# trailmon.net
KiCad netlist of a schematic drawn in EAGLE
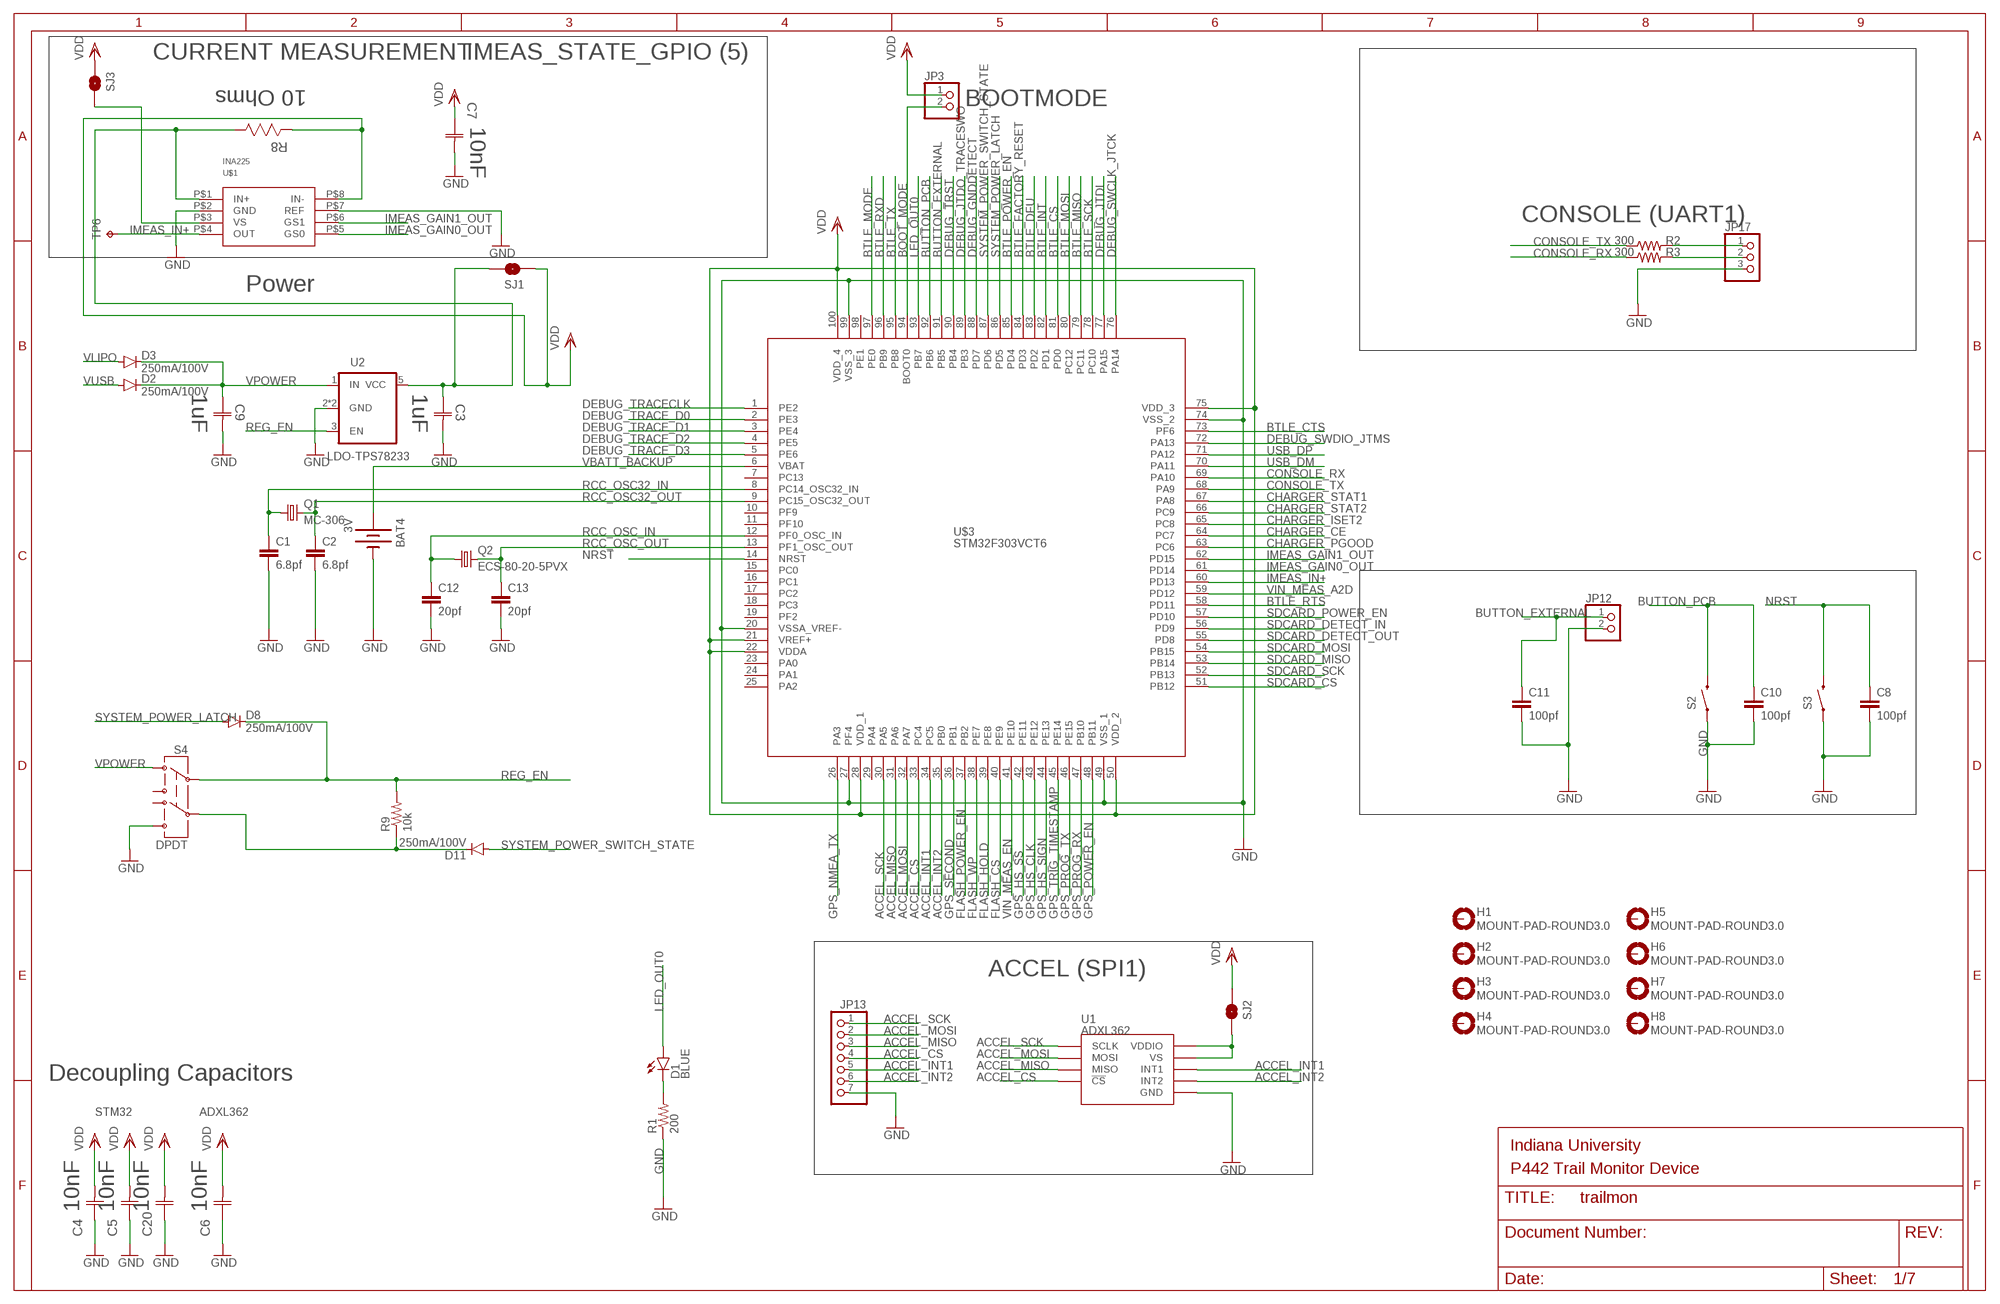
[diagram p0: schematic, sheet 1]
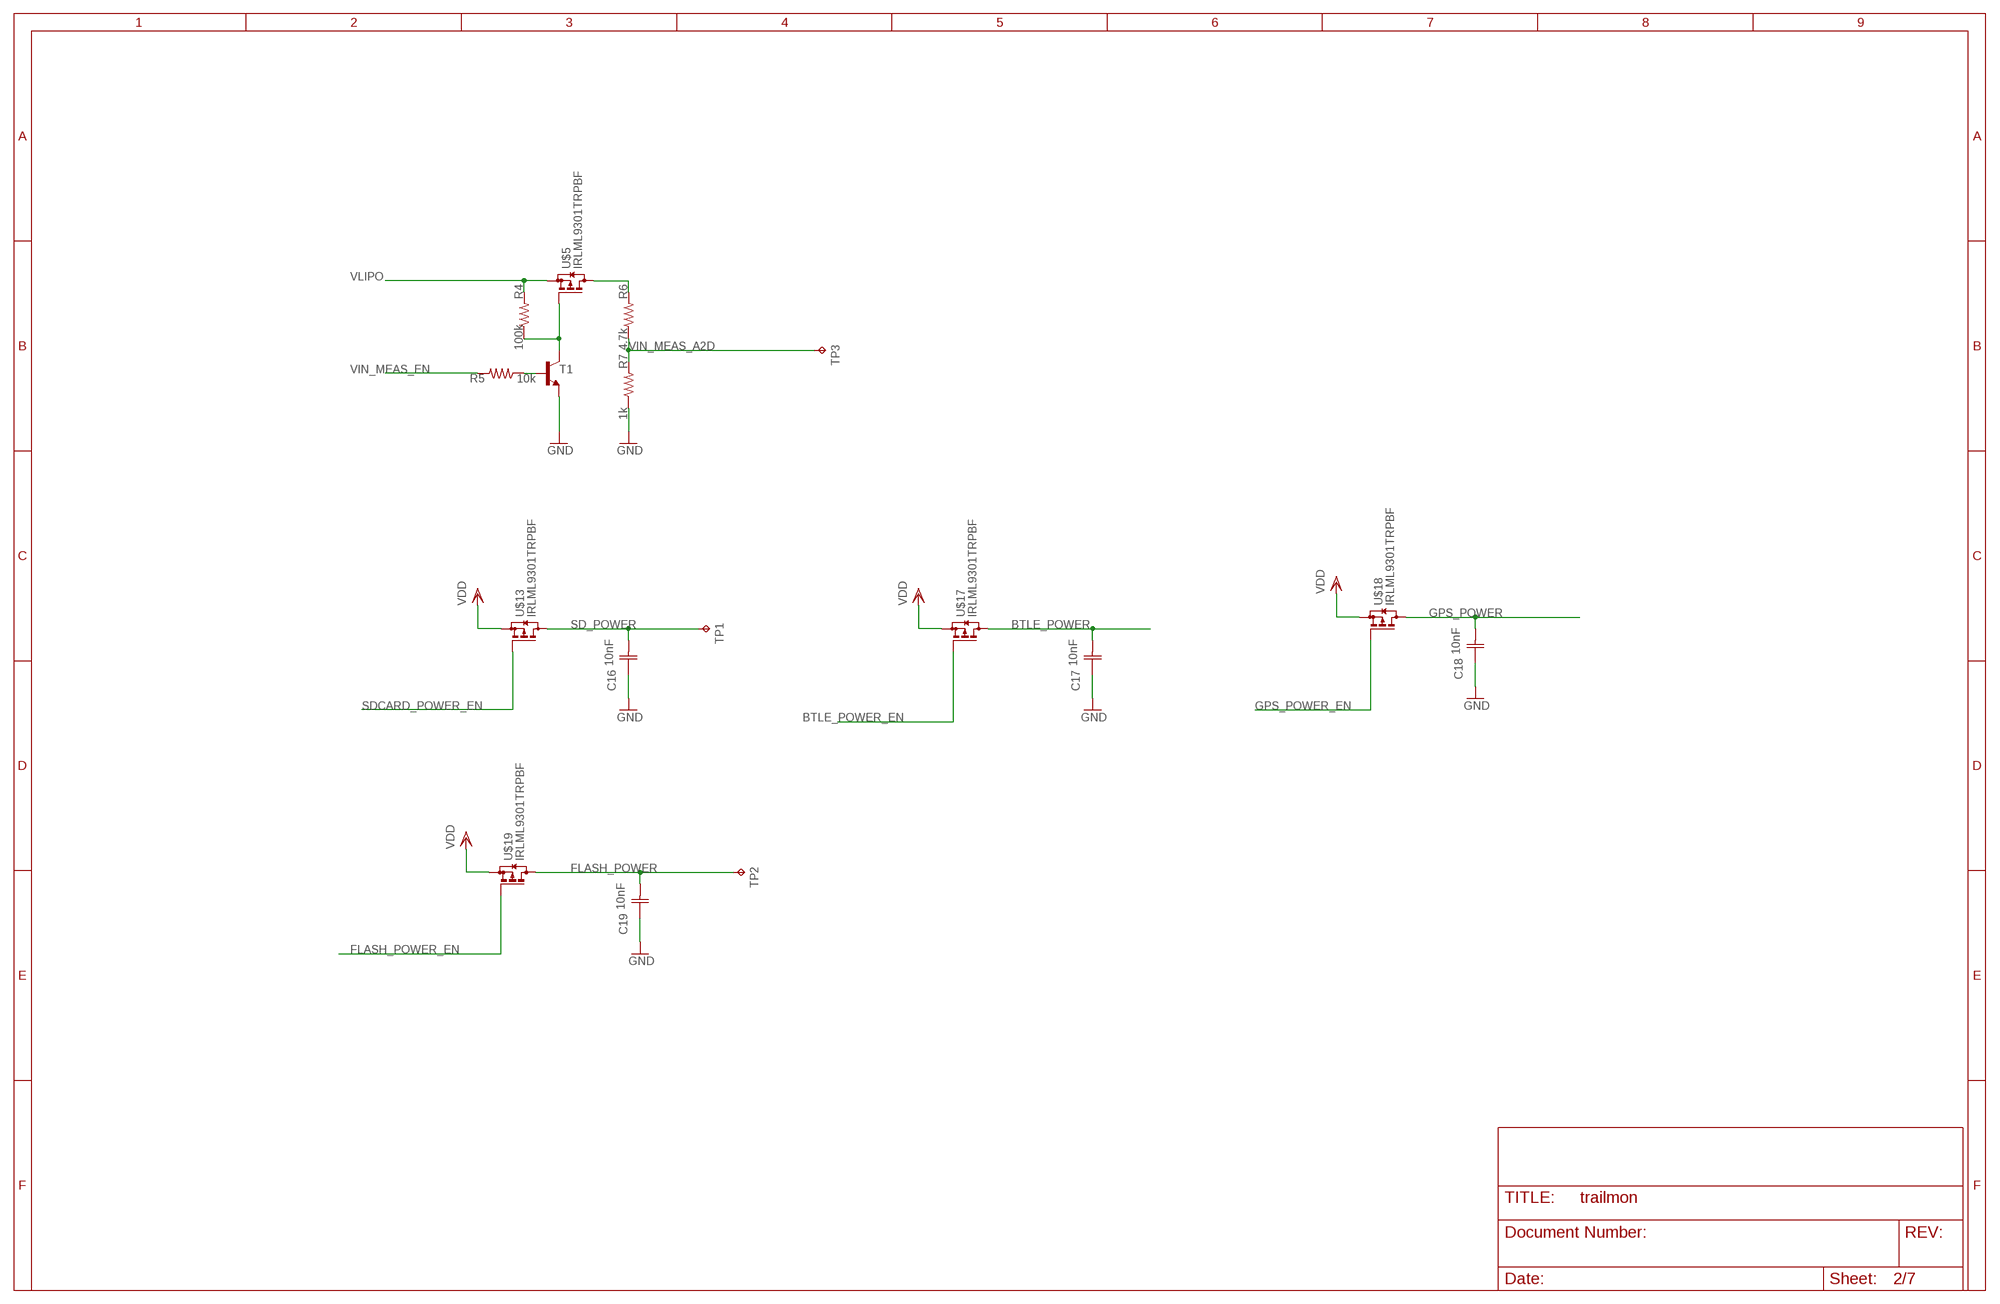
[diagram p1: schematic, sheet 2]
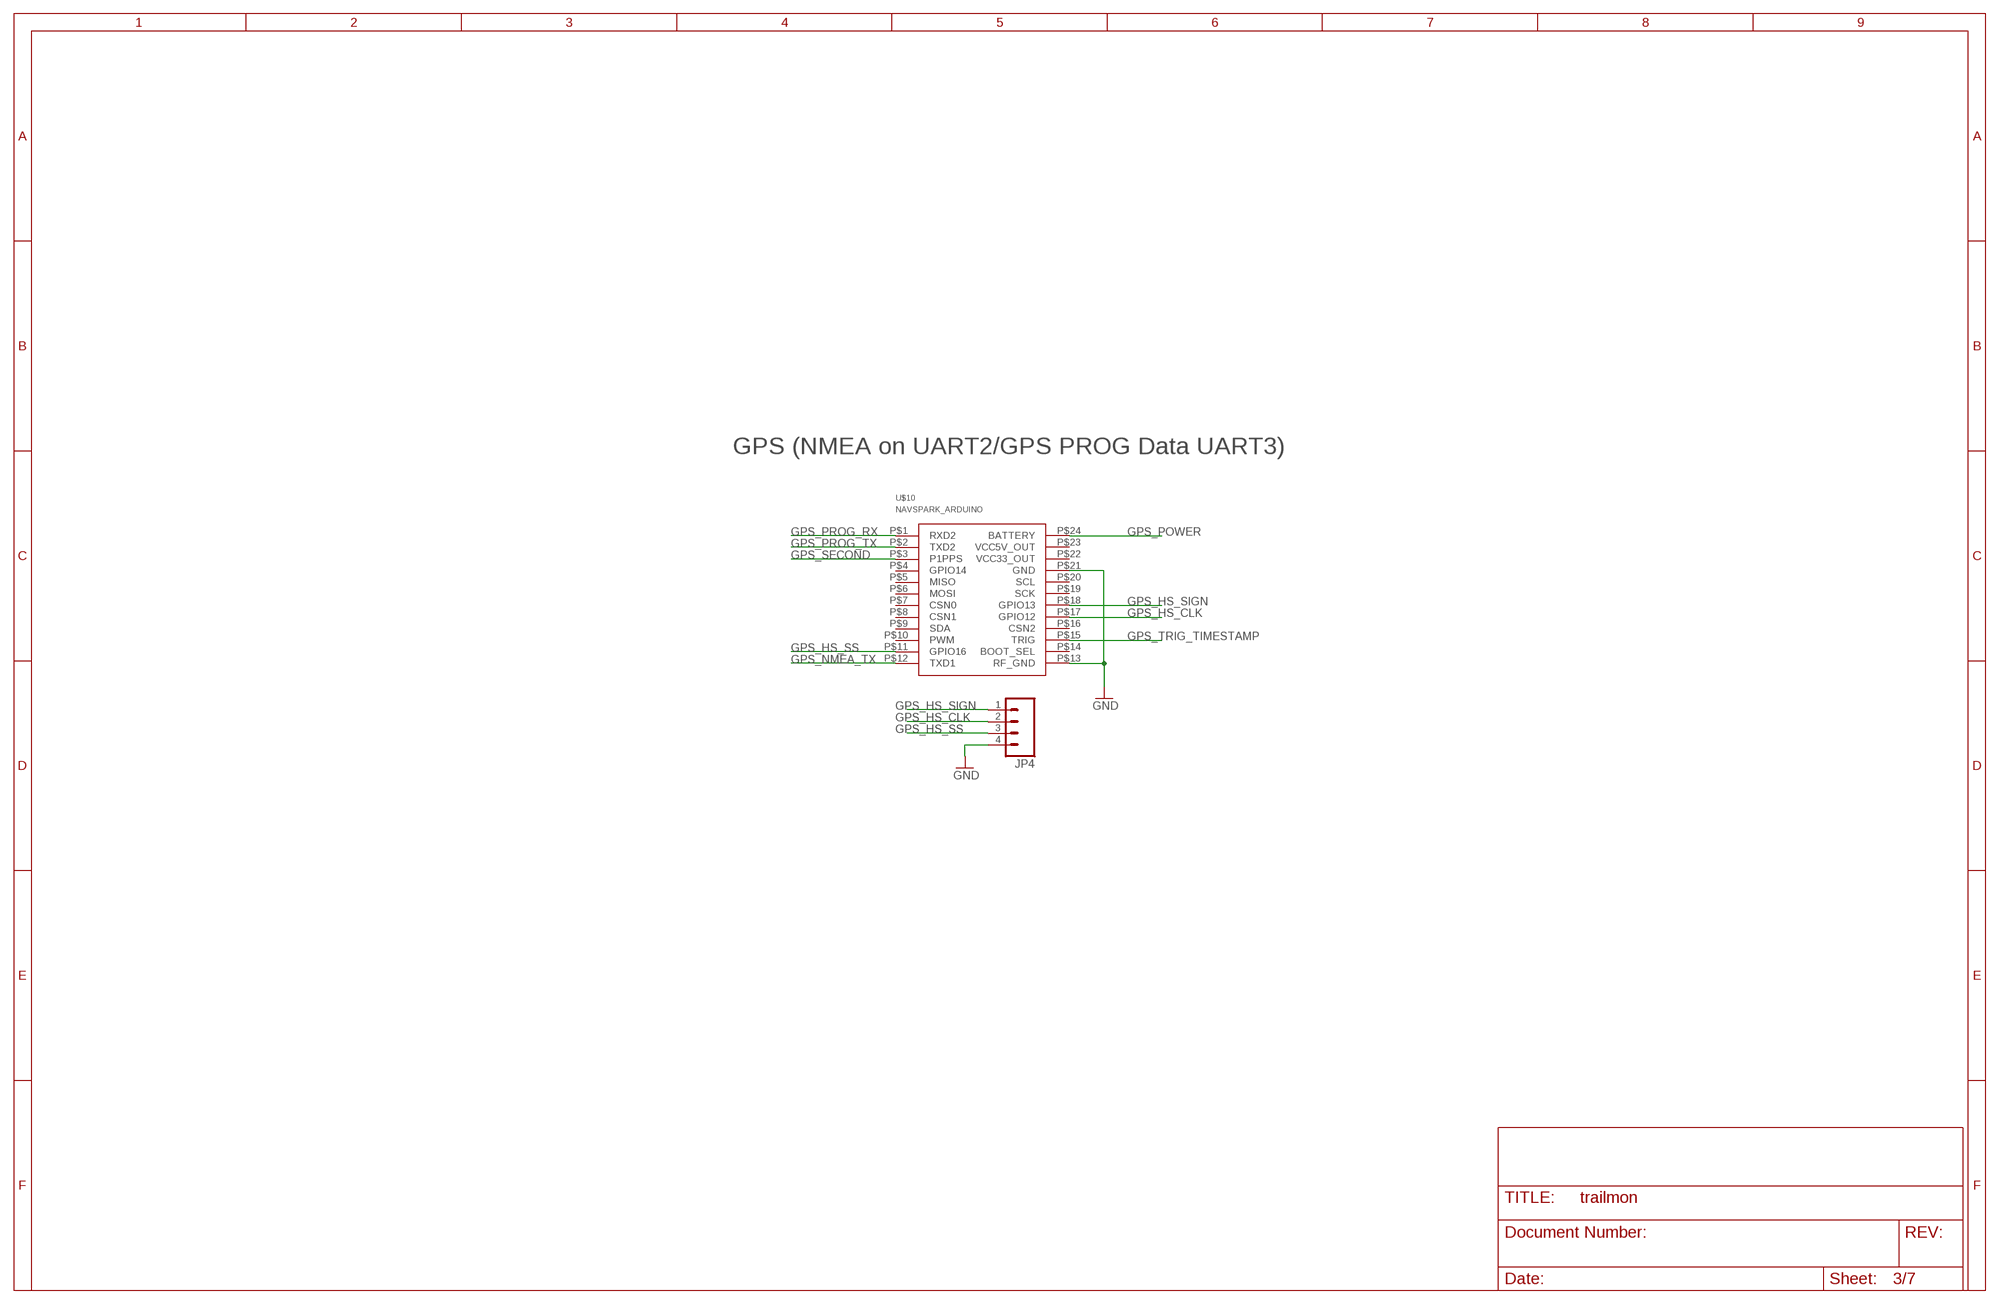
[diagram p2: schematic, sheet 3]
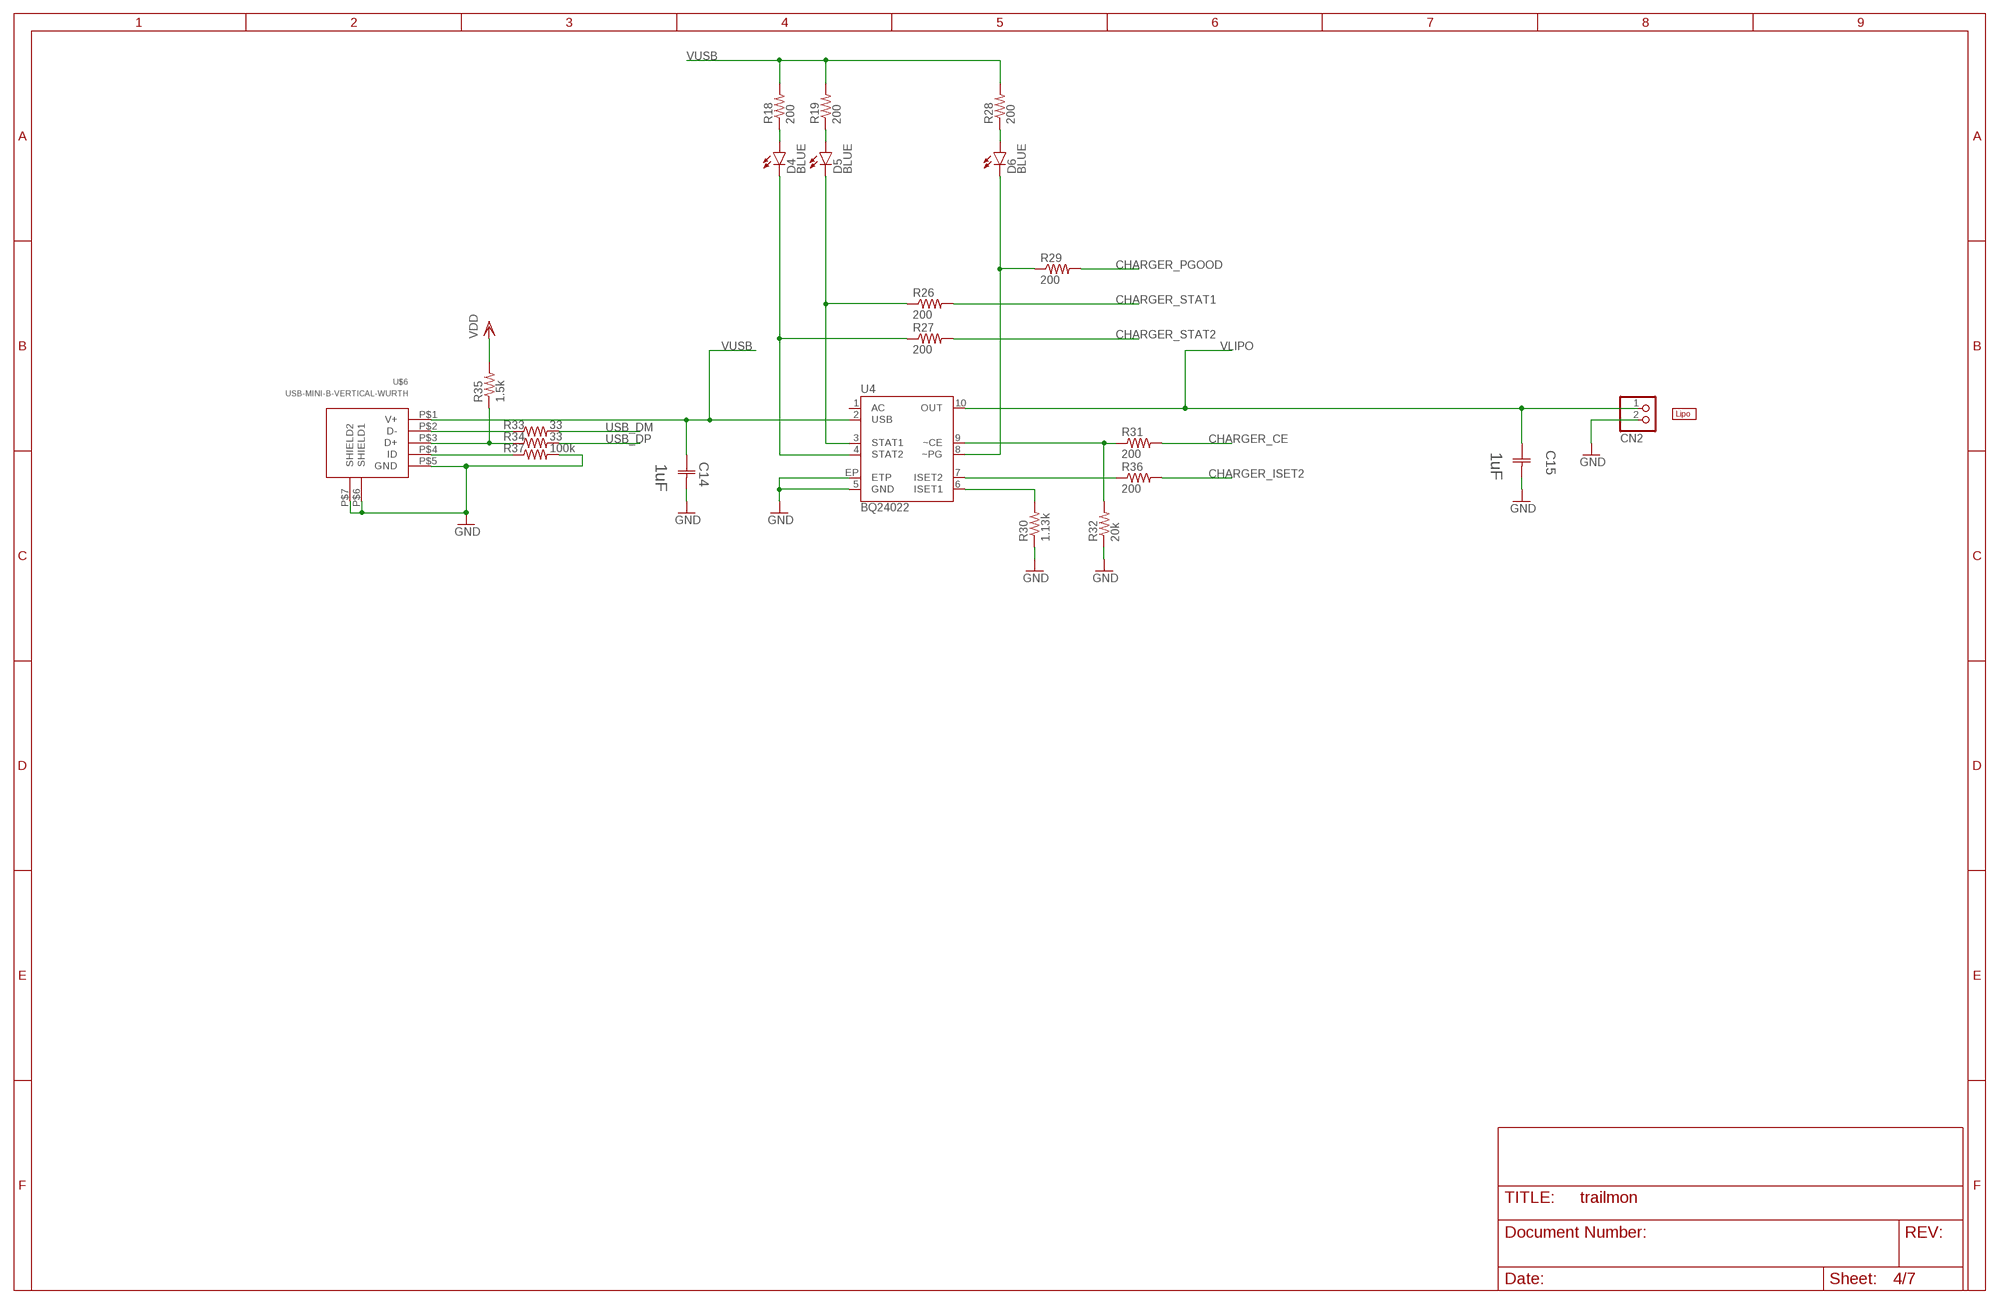
[diagram p3: schematic, sheet 4]
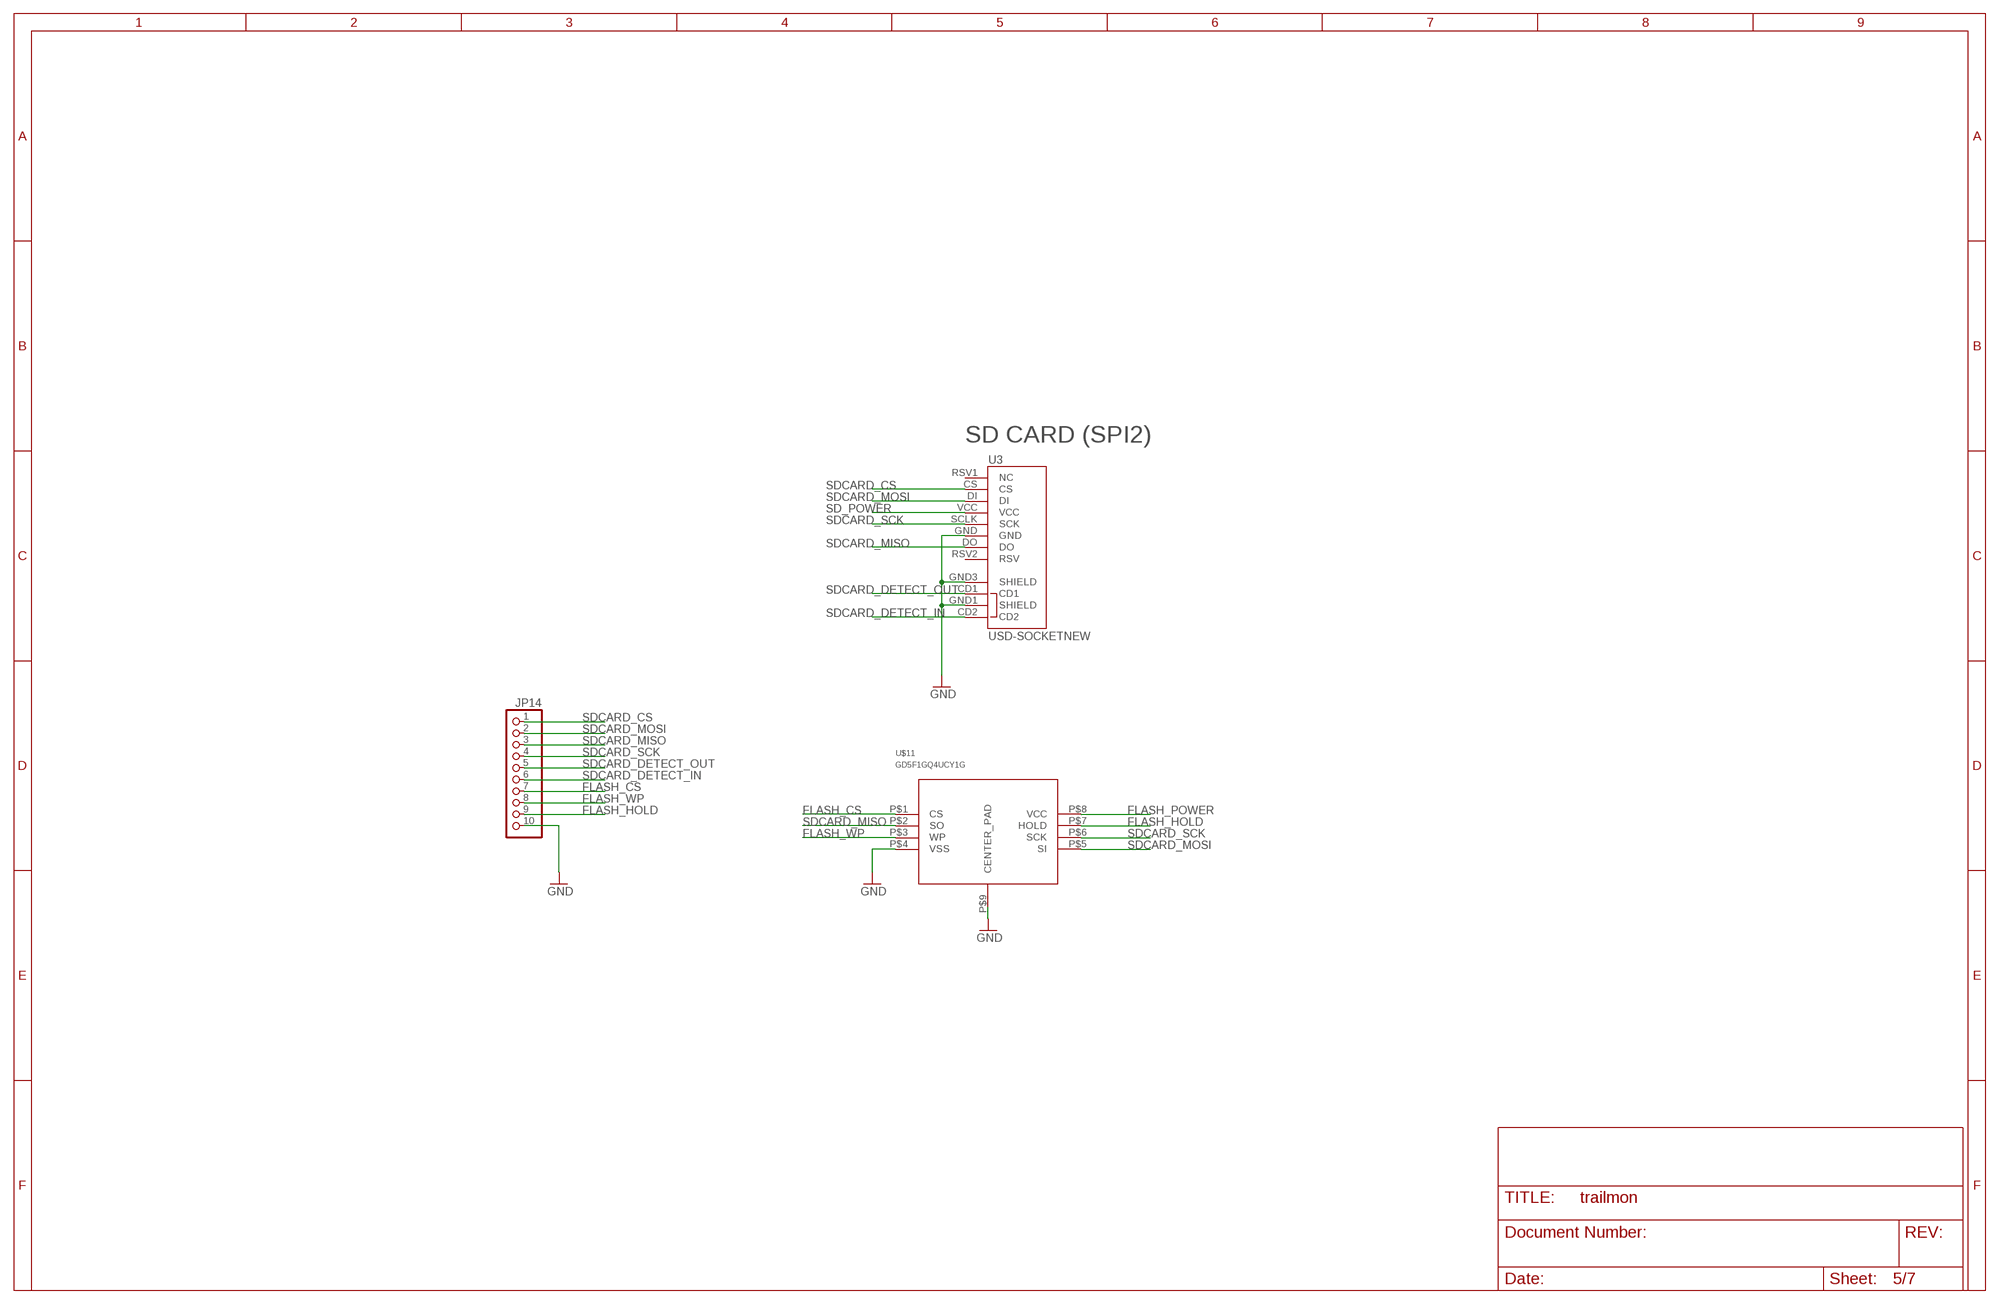
[diagram p4: schematic, sheet 5]
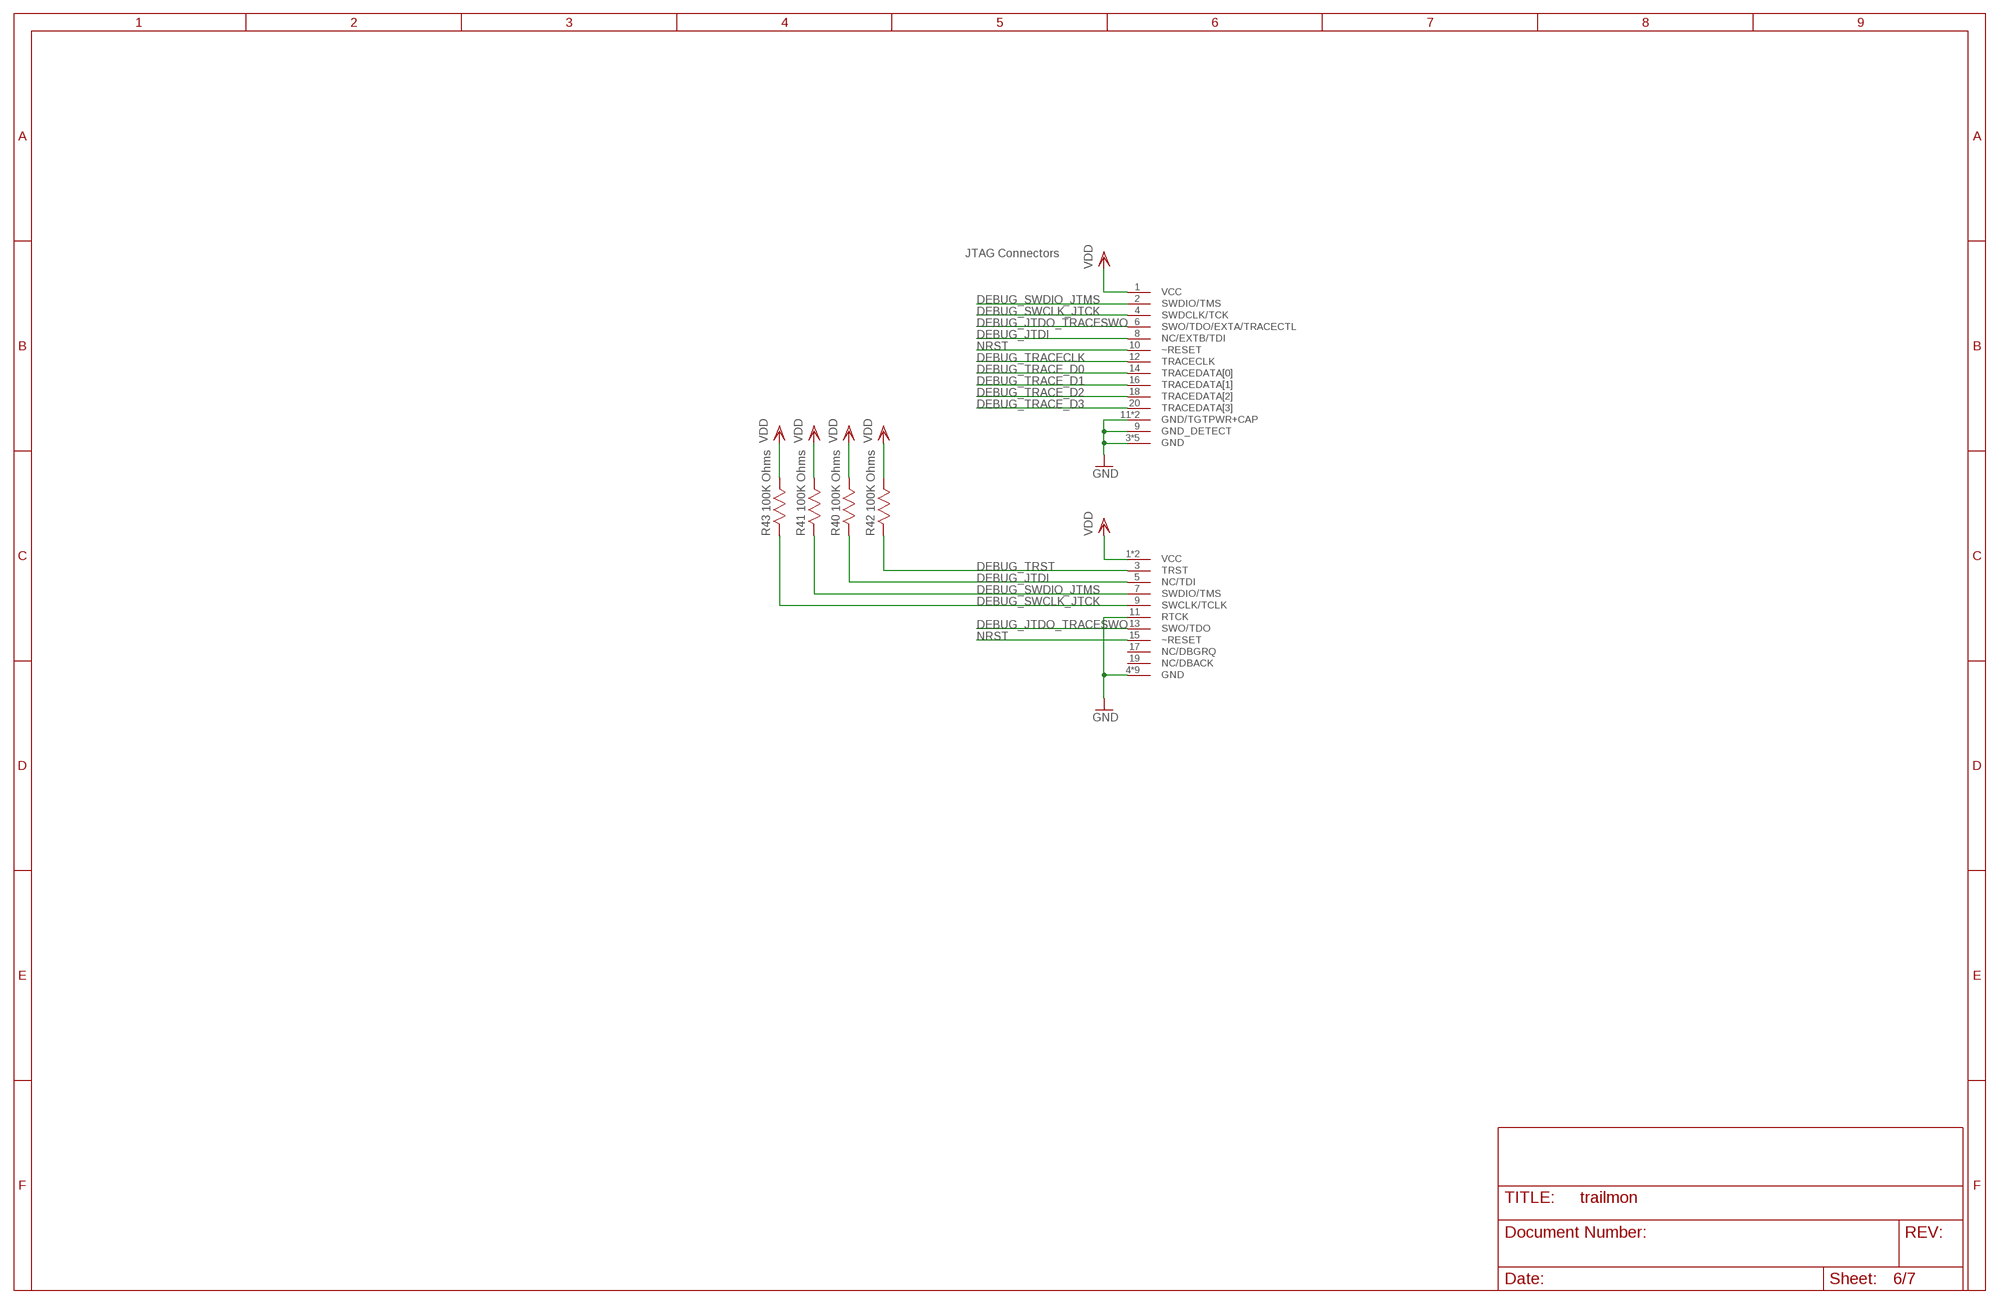
[diagram p5: schematic, sheet 6]
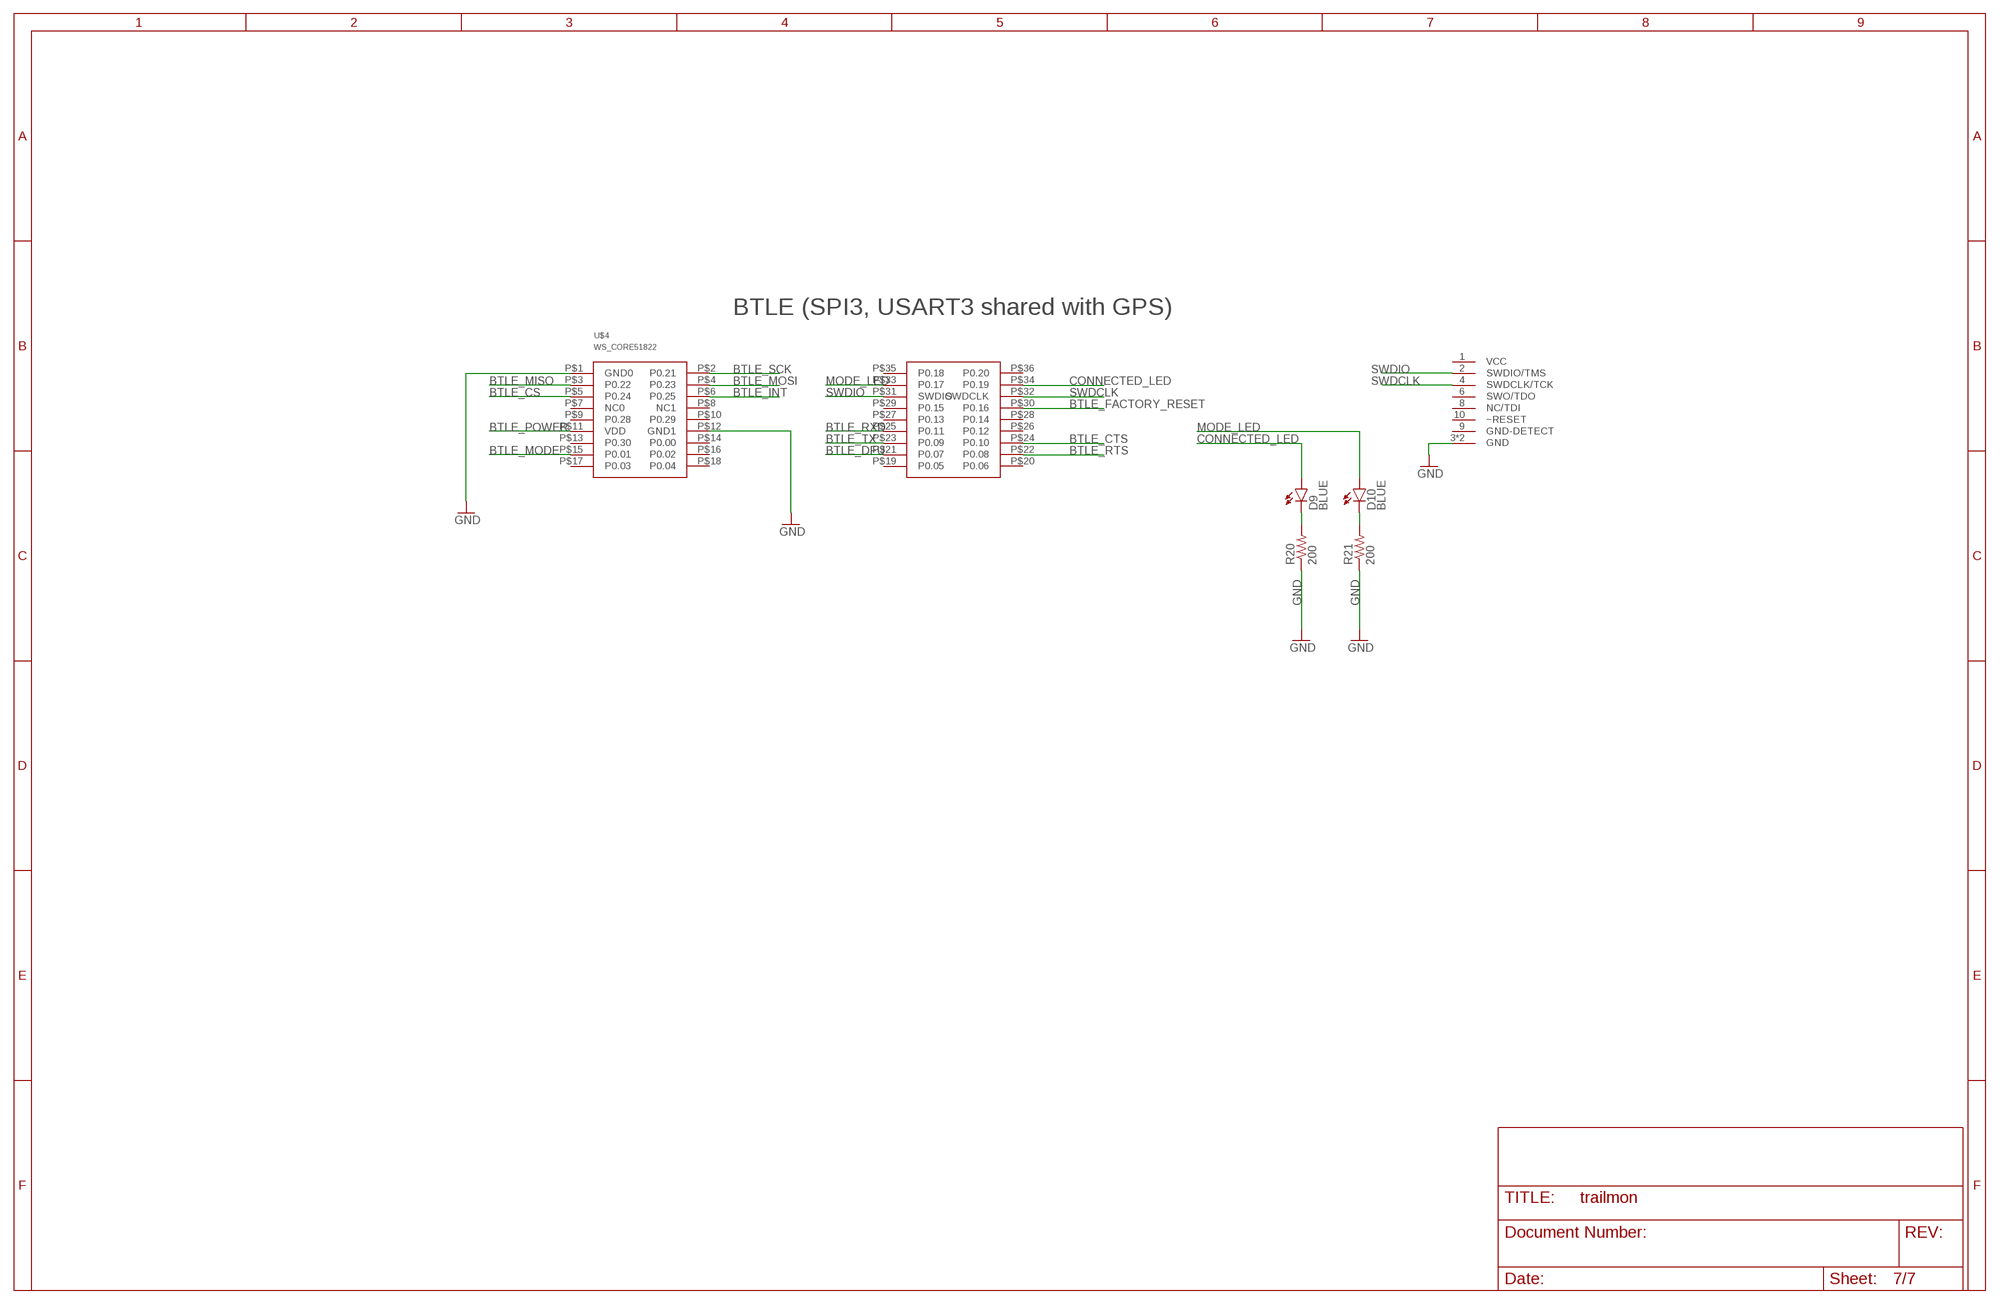
[diagram p6: schematic, sheet 7]

(export (version "E")
  (design (tool "Eeschema 10.0.6"))
  (components
    (comp (ref "JP14")
      (value "PINHD-1X10")
      (footprint "eagle-import:1X10")
      (libsource (lib "eagle-import") (part "PINHD-1X10"))
    )
    (comp (ref "U$11")
      (value "GD5F1GQ4UCY1G")
      (footprint "eagle-import:WSON-8")
      (libsource (lib "eagle-import") (part "GD5F1GQ4UCY1G"))
    )
    (comp (ref "U3")
      (value "USD-SOCKETNEW")
      (footprint "eagle-import:MICRO-SD-SOCKET-PP")
      (libsource (lib "eagle-import") (part "USD-SOCKETNEW"))
    )
    (comp (ref "R40")
      (value "100K Ohms")
      (footprint "eagle-import:RESC1005X40N")
      (fields (field (name "MPN") "CRCW0402100KFKED") (field (name "TOLERANCE") "±1%"))
      (libsource (lib "eagle-import") (part "CRCW0402100KFKED"))
    )
    (comp (ref "R41")
      (value "100K Ohms")
      (footprint "eagle-import:RESC1005X40N")
      (fields (field (name "MPN") "CRCW0402100KFKED") (field (name "TOLERANCE") "±1%"))
      (libsource (lib "eagle-import") (part "CRCW0402100KFKED"))
    )
    (comp (ref "R42")
      (value "100K Ohms")
      (footprint "eagle-import:RESC1005X40N")
      (fields (field (name "MPN") "CRCW0402100KFKED") (field (name "TOLERANCE") "±1%"))
      (libsource (lib "eagle-import") (part "CRCW0402100KFKED"))
    )
    (comp (ref "R43")
      (value "100K Ohms")
      (footprint "eagle-import:RESC1005X40N")
      (fields (field (name "MPN") "CRCW0402100KFKED") (field (name "TOLERANCE") "±1%"))
      (libsource (lib "eagle-import") (part "CRCW0402100KFKED"))
    )
    (comp (ref "U$2")
      (value "2X10_0.05\"_CORTEX_DEBUG_WITH_ETMSMD_UNSHROUDED")
      (footprint "eagle-import:2X10_0.05__SMD_NS")
      (libsource (lib "eagle-import") (part "2X10_0.05{dblquote}_CORTEX_DEBUG_WITH_ETMSMD_UNSHROUDED"))
    )
    (comp (ref "U$12")
      (value "TRADITIONALJTAG/SWDTH_SHROUDED")
      (footprint "eagle-import:2X10_0.1__TH_SH")
      (libsource (lib "eagle-import") (part "TRADITIONALJTAG/SWDTH_SHROUDED"))
    )
    (comp (ref "JP4")
      (value "M04PTH")
      (footprint "eagle-import:1X04")
      (libsource (lib "eagle-import") (part "M04PTH"))
    )
    (comp (ref "U$10")
      (value "NAVSPARK_ARDUINO")
      (footprint "eagle-import:NAVSPARK_ARDUINO")
      (libsource (lib "eagle-import") (part "NAVSPARK_ARDUINO"))
    )
    (comp (ref "BAT4")
      (value "3V")
      (footprint "eagle-import:BATTCON_12MM")
      (libsource (lib "eagle-import") (part "BATTERY12MM"))
    )
    (comp (ref "C1")
      (value "6.8pf")
      (footprint "eagle-import:0603-CAP")
      (libsource (lib "eagle-import") (part "CAP0603-CAP"))
    )
    (comp (ref "C2")
      (value "6.8pf")
      (footprint "eagle-import:0603-CAP")
      (libsource (lib "eagle-import") (part "CAP0603-CAP"))
    )
    (comp (ref "C3")
      (value "1uF")
      (footprint "eagle-import:CAPC2013X110N")
      (fields (field (name "MPN") "C0805C105K4RACTU") (field (name "TOLERANCE") "±10%"))
      (libsource (lib "eagle-import") (part "C0805C105K4RACTU"))
    )
    (comp (ref "C4")
      (value "10nF")
      (footprint "eagle-import:CAPC2013X88N")
      (fields (field (name "MPN") "C0805C103K5RACTU") (field (name "TOLERANCE") "±10%"))
      (libsource (lib "eagle-import") (part "C0805C103K5RACTU"))
    )
    (comp (ref "C5")
      (value "10nF")
      (footprint "eagle-import:CAPC2013X88N")
      (fields (field (name "MPN") "C0805C103K5RACTU") (field (name "TOLERANCE") "±10%"))
      (libsource (lib "eagle-import") (part "C0805C103K5RACTU"))
    )
    (comp (ref "C6")
      (value "10nF")
      (footprint "eagle-import:CAPC2013X88N")
      (fields (field (name "MPN") "C0805C103K5RACTU") (field (name "TOLERANCE") "±10%"))
      (libsource (lib "eagle-import") (part "C0805C103K5RACTU"))
    )
    (comp (ref "C7")
      (value "10nF")
      (footprint "eagle-import:CAPC2013X88N")
      (fields (field (name "MPN") "C0805C103K5RACTU") (field (name "TOLERANCE") "±10%"))
      (libsource (lib "eagle-import") (part "C0805C103K5RACTU"))
    )
    (comp (ref "C8")
      (value "100pf")
      (footprint "eagle-import:0805")
      (libsource (lib "eagle-import") (part "CAP0805"))
    )
    (comp (ref "C9")
      (value "1uF")
      (footprint "eagle-import:CAPC2013X110N")
      (fields (field (name "MPN") "C0805C105K4RACTU") (field (name "TOLERANCE") "±10%"))
      (libsource (lib "eagle-import") (part "C0805C105K4RACTU"))
    )
    (comp (ref "C10")
      (value "100pf")
      (footprint "eagle-import:0805")
      (libsource (lib "eagle-import") (part "CAP0805"))
    )
    (comp (ref "C11")
      (value "100pf")
      (footprint "eagle-import:0805")
      (libsource (lib "eagle-import") (part "CAP0805"))
    )
    (comp (ref "C12")
      (value "20pf")
      (footprint "eagle-import:0603-CAP")
      (libsource (lib "eagle-import") (part "CAP0603-CAP"))
    )
    (comp (ref "C13")
      (value "20pf")
      (footprint "eagle-import:0603-CAP")
      (libsource (lib "eagle-import") (part "CAP0603-CAP"))
    )
    (comp (ref "C20")
      (value "10nF")
      (footprint "eagle-import:CAPC2013X88N")
      (fields (field (name "MPN") "C0805C103K5RACTU") (field (name "TOLERANCE") "±10%"))
      (libsource (lib "eagle-import") (part "C0805C103K5RACTU"))
    )
    (comp (ref "D1")
      (value "BLUE")
      (footprint "eagle-import:LED-0603")
      (libsource (lib "eagle-import") (part "LED-BLUE0603"))
    )
    (comp (ref "D2")
      (value "250mA/100V")
      (footprint "eagle-import:SOD-323")
      (libsource (lib "eagle-import") (part "DIODEBAS16"))
    )
    (comp (ref "D3")
      (value "250mA/100V")
      (footprint "eagle-import:SOD-323")
      (libsource (lib "eagle-import") (part "DIODEBAS16"))
    )
    (comp (ref "D8")
      (value "250mA/100V")
      (footprint "eagle-import:SOD-323")
      (libsource (lib "eagle-import") (part "DIODEBAS16"))
    )
    (comp (ref "D11")
      (value "250mA/100V")
      (footprint "eagle-import:SOD-323")
      (libsource (lib "eagle-import") (part "DIODEBAS16"))
    )
    (comp (ref "H1")
      (value "MOUNT-PAD-ROUND3.0")
      (footprint "eagle-import:3,0-PAD")
      (libsource (lib "eagle-import") (part "MOUNT-PAD-ROUND3.0"))
    )
    (comp (ref "H2")
      (value "MOUNT-PAD-ROUND3.0")
      (footprint "eagle-import:3,0-PAD")
      (libsource (lib "eagle-import") (part "MOUNT-PAD-ROUND3.0"))
    )
    (comp (ref "H3")
      (value "MOUNT-PAD-ROUND3.0")
      (footprint "eagle-import:3,0-PAD")
      (libsource (lib "eagle-import") (part "MOUNT-PAD-ROUND3.0"))
    )
    (comp (ref "H4")
      (value "MOUNT-PAD-ROUND3.0")
      (footprint "eagle-import:3,0-PAD")
      (libsource (lib "eagle-import") (part "MOUNT-PAD-ROUND3.0"))
    )
    (comp (ref "H5")
      (value "MOUNT-PAD-ROUND3.0")
      (footprint "eagle-import:3,0-PAD")
      (libsource (lib "eagle-import") (part "MOUNT-PAD-ROUND3.0"))
    )
    (comp (ref "H6")
      (value "MOUNT-PAD-ROUND3.0")
      (footprint "eagle-import:3,0-PAD")
      (libsource (lib "eagle-import") (part "MOUNT-PAD-ROUND3.0"))
    )
    (comp (ref "H7")
      (value "MOUNT-PAD-ROUND3.0")
      (footprint "eagle-import:3,0-PAD")
      (libsource (lib "eagle-import") (part "MOUNT-PAD-ROUND3.0"))
    )
    (comp (ref "H8")
      (value "MOUNT-PAD-ROUND3.0")
      (footprint "eagle-import:3,0-PAD")
      (libsource (lib "eagle-import") (part "MOUNT-PAD-ROUND3.0"))
    )
    (comp (ref "JP3")
      (value "PINHD-1X2")
      (footprint "eagle-import:1X02")
      (libsource (lib "eagle-import") (part "PINHD-1X2"))
    )
    (comp (ref "JP12")
      (value "PINHD-1X2")
      (footprint "eagle-import:1X02")
      (libsource (lib "eagle-import") (part "PINHD-1X2"))
    )
    (comp (ref "JP13")
      (value "PINHD-1X7")
      (footprint "eagle-import:1X07")
      (libsource (lib "eagle-import") (part "PINHD-1X7"))
    )
    (comp (ref "JP17")
      (value "PINHD-1X3")
      (footprint "eagle-import:1X03")
      (libsource (lib "eagle-import") (part "PINHD-1X3"))
    )
    (comp (ref "Q1")
      (value "MC-306")
      (footprint "eagle-import:MC-306")
      (fields (field (name "MPN") "MC-306 60.0KHZ  100PPM ,12.5PF"))
      (libsource (lib "eagle-import") (part "MC-306"))
    )
    (comp (ref "Q2")
      (value "ECS-80-20-5PVX")
      (footprint "eagle-import:CSM-7X-DU")
      (libsource (lib "eagle-import") (part "CSM-7X-DU"))
    )
    (comp (ref "R1")
      (value "200")
      (footprint "eagle-import:0603-RES")
      (libsource (lib "eagle-import") (part "RESISTOR0603-RES"))
    )
    (comp (ref "R2")
      (value "300")
      (footprint "eagle-import:0805")
      (libsource (lib "eagle-import") (part "RESISTOR0805-RES"))
    )
    (comp (ref "R3")
      (value "300")
      (footprint "eagle-import:0805")
      (libsource (lib "eagle-import") (part "RESISTOR0805-RES"))
    )
    (comp (ref "R8")
      (value "10 Ohms")
      (footprint "eagle-import:RESC1608X60N")
      (fields (field (name "MPN") "TNPW060310R0BEEN") (field (name "TOLERANCE") "± 0.1 %"))
      (libsource (lib "eagle-import") (part "TNPW060310R0BEEN"))
    )
    (comp (ref "R9")
      (value "10k")
      (footprint "eagle-import:0603-RES")
      (libsource (lib "eagle-import") (part "RESISTOR0603-RES"))
    )
    (comp (ref "S2")
      (value "SWITCH-MOMENTARY-2SMD")
      (footprint "eagle-import:TACTILE-SWITCH-SMD")
      (libsource (lib "eagle-import") (part "SWITCH-MOMENTARY-2SMD"))
    )
    (comp (ref "S3")
      (value "SWITCH-MOMENTARY-2SMD")
      (footprint "eagle-import:TACTILE-SWITCH-SMD")
      (libsource (lib "eagle-import") (part "SWITCH-MOMENTARY-2SMD"))
    )
    (comp (ref "S4")
      (value "DPDT")
      (footprint "eagle-import:AYZ0202")
      (libsource (lib "eagle-import") (part "SWITCH-DPDTAYZ0202"))
    )
    (comp (ref "SJ1")
      (value "JUMPER-PAD-2-NOYES_SILK")
      (footprint "eagle-import:PAD-JUMPER-2-NO_YES_SILK")
      (libsource (lib "eagle-import") (part "JUMPER-PAD-2-NOYES_SILK"))
    )
    (comp (ref "SJ2")
      (value "JUMPER-PAD-2-NOYES_SILK")
      (footprint "eagle-import:PAD-JUMPER-2-NO_YES_SILK")
      (libsource (lib "eagle-import") (part "JUMPER-PAD-2-NOYES_SILK"))
    )
    (comp (ref "SJ3")
      (value "JUMPER-PAD-2-NOYES_SILK")
      (footprint "eagle-import:PAD-JUMPER-2-NO_YES_SILK")
      (libsource (lib "eagle-import") (part "JUMPER-PAD-2-NOYES_SILK"))
    )
    (comp (ref "TP6")
      (value "TPB1,27")
      (footprint "eagle-import:B1,27")
      (libsource (lib "eagle-import") (part "TPB1,27"))
    )
    (comp (ref "U$1")
      (value "INA225")
      (footprint "eagle-import:MSOP-8")
      (libsource (lib "eagle-import") (part "INA225"))
    )
    (comp (ref "U$3")
      (value "STM32F303VCT6")
      (footprint "eagle-import:TQFP100")
      (libsource (lib "eagle-import") (part "STM32F303VCT6"))
    )
    (comp (ref "U1")
      (value "ADXL362")
      (footprint "eagle-import:ADXL362")
      (libsource (lib "eagle-import") (part "ADXL362"))
    )
    (comp (ref "U2")
      (value "LDO-TPS78233")
      (footprint "eagle-import:SOT23-5")
      (libsource (lib "eagle-import") (part "LDO-TPS78233"))
    )
    (comp (ref "C16")
      (value "10nF")
      (footprint "eagle-import:CAPC2013X88N")
      (fields (field (name "MPN") "C0805C103K5RACTU") (field (name "TOLERANCE") "±10%"))
      (libsource (lib "eagle-import") (part "C0805C103K5RACTU"))
    )
    (comp (ref "C17")
      (value "10nF")
      (footprint "eagle-import:CAPC2013X88N")
      (fields (field (name "MPN") "C0805C103K5RACTU") (field (name "TOLERANCE") "±10%"))
      (libsource (lib "eagle-import") (part "C0805C103K5RACTU"))
    )
    (comp (ref "C18")
      (value "10nF")
      (footprint "eagle-import:CAPC2013X88N")
      (fields (field (name "MPN") "C0805C103K5RACTU") (field (name "TOLERANCE") "±10%"))
      (libsource (lib "eagle-import") (part "C0805C103K5RACTU"))
    )
    (comp (ref "C19")
      (value "10nF")
      (footprint "eagle-import:CAPC2013X88N")
      (fields (field (name "MPN") "C0805C103K5RACTU") (field (name "TOLERANCE") "±10%"))
      (libsource (lib "eagle-import") (part "C0805C103K5RACTU"))
    )
    (comp (ref "R4")
      (value "100k")
      (footprint "eagle-import:0805")
      (libsource (lib "eagle-import") (part "RESISTOR0805-RES"))
    )
    (comp (ref "R5")
      (value "10k")
      (footprint "eagle-import:0805")
      (libsource (lib "eagle-import") (part "RESISTOR0805-RES"))
    )
    (comp (ref "R6")
      (value "4.7k")
      (footprint "eagle-import:0805")
      (libsource (lib "eagle-import") (part "RESISTOR0805-RES"))
    )
    (comp (ref "R7")
      (value "1k")
      (footprint "eagle-import:0805")
      (libsource (lib "eagle-import") (part "RESISTOR0805-RES"))
    )
    (comp (ref "T1")
      (value "BC847")
      (footprint "eagle-import:SOT23")
      (libsource (lib "eagle-import") (part "BC847"))
    )
    (comp (ref "TP1")
      (value "TPB1,27")
      (footprint "eagle-import:B1,27")
      (libsource (lib "eagle-import") (part "TPB1,27"))
    )
    (comp (ref "TP2")
      (value "TPB1,27")
      (footprint "eagle-import:B1,27")
      (libsource (lib "eagle-import") (part "TPB1,27"))
    )
    (comp (ref "TP3")
      (value "TPB1,27")
      (footprint "eagle-import:B1,27")
      (libsource (lib "eagle-import") (part "TPB1,27"))
    )
    (comp (ref "U$5")
      (value "IRLML9301TRPBF")
      (footprint "eagle-import:SOT23")
      (libsource (lib "eagle-import") (part "IRLML9301TRPBF"))
    )
    (comp (ref "U$13")
      (value "IRLML9301TRPBF")
      (footprint "eagle-import:SOT23")
      (libsource (lib "eagle-import") (part "IRLML9301TRPBF"))
    )
    (comp (ref "U$17")
      (value "IRLML9301TRPBF")
      (footprint "eagle-import:SOT23")
      (libsource (lib "eagle-import") (part "IRLML9301TRPBF"))
    )
    (comp (ref "U$18")
      (value "IRLML9301TRPBF")
      (footprint "eagle-import:SOT23")
      (libsource (lib "eagle-import") (part "IRLML9301TRPBF"))
    )
    (comp (ref "U$19")
      (value "IRLML9301TRPBF")
      (footprint "eagle-import:SOT23")
      (libsource (lib "eagle-import") (part "IRLML9301TRPBF"))
    )
    (comp (ref "C14")
      (value "1uF")
      (footprint "eagle-import:CAPC2013X110N")
      (fields (field (name "MPN") "C0805C105K4RACTU") (field (name "TOLERANCE") "±10%"))
      (libsource (lib "eagle-import") (part "C0805C105K4RACTU"))
    )
    (comp (ref "C15")
      (value "1uF")
      (footprint "eagle-import:CAPC2013X110N")
      (fields (field (name "MPN") "C0805C105K4RACTU") (field (name "TOLERANCE") "±10%"))
      (libsource (lib "eagle-import") (part "C0805C105K4RACTU"))
    )
    (comp (ref "CN2")
      (value "JST_2PIN-THM")
      (footprint "eagle-import:JST-PH-2-THM")
      (libsource (lib "eagle-import") (part "JST_2PIN-THM"))
    )
    (comp (ref "D4")
      (value "BLUE")
      (footprint "eagle-import:LED-0603")
      (libsource (lib "eagle-import") (part "LED-BLUE0603"))
    )
    (comp (ref "D5")
      (value "BLUE")
      (footprint "eagle-import:LED-0603")
      (libsource (lib "eagle-import") (part "LED-BLUE0603"))
    )
    (comp (ref "D6")
      (value "BLUE")
      (footprint "eagle-import:LED-0603")
      (libsource (lib "eagle-import") (part "LED-BLUE0603"))
    )
    (comp (ref "R18")
      (value "200")
      (footprint "eagle-import:0603-RES")
      (libsource (lib "eagle-import") (part "RESISTOR0603-RES"))
    )
    (comp (ref "R19")
      (value "200")
      (footprint "eagle-import:0603-RES")
      (libsource (lib "eagle-import") (part "RESISTOR0603-RES"))
    )
    (comp (ref "R26")
      (value "200")
      (footprint "eagle-import:0603-RES")
      (libsource (lib "eagle-import") (part "RESISTOR0603-RES"))
    )
    (comp (ref "R27")
      (value "200")
      (footprint "eagle-import:0603-RES")
      (libsource (lib "eagle-import") (part "RESISTOR0603-RES"))
    )
    (comp (ref "R28")
      (value "200")
      (footprint "eagle-import:0603-RES")
      (libsource (lib "eagle-import") (part "RESISTOR0603-RES"))
    )
    (comp (ref "R29")
      (value "200")
      (footprint "eagle-import:0603-RES")
      (libsource (lib "eagle-import") (part "RESISTOR0603-RES"))
    )
    (comp (ref "R30")
      (value "1.13k")
      (footprint "eagle-import:0603-RES")
      (libsource (lib "eagle-import") (part "RESISTOR0603-RES"))
    )
    (comp (ref "R31")
      (value "200")
      (footprint "eagle-import:0603-RES")
      (libsource (lib "eagle-import") (part "RESISTOR0603-RES"))
    )
    (comp (ref "R32")
      (value "20k")
      (footprint "eagle-import:0603-RES")
      (libsource (lib "eagle-import") (part "RESISTOR0603-RES"))
    )
    (comp (ref "R33")
      (value "33")
      (footprint "eagle-import:0603-RES")
      (libsource (lib "eagle-import") (part "RESISTOR0603-RES"))
    )
    (comp (ref "R34")
      (value "33")
      (footprint "eagle-import:0603-RES")
      (libsource (lib "eagle-import") (part "RESISTOR0603-RES"))
    )
    (comp (ref "R35")
      (value "1.5k")
      (footprint "eagle-import:0603-RES")
      (libsource (lib "eagle-import") (part "RESISTOR0603-RES"))
    )
    (comp (ref "R36")
      (value "200")
      (footprint "eagle-import:0603-RES")
      (libsource (lib "eagle-import") (part "RESISTOR0603-RES"))
    )
    (comp (ref "R37")
      (value "100k")
      (footprint "eagle-import:0603-RES")
      (libsource (lib "eagle-import") (part "RESISTOR0603-RES"))
    )
    (comp (ref "U$6")
      (value "USB-MINI-B-VERTICAL-WURTH")
      (footprint "eagle-import:MINI-B-VERTICAL-WURTH")
      (libsource (lib "eagle-import") (part "USB-MINI-B-VERTICAL-WURTH"))
    )
    (comp (ref "U$16")
      (value "LIPO-OUTLINE1100")
      (footprint "eagle-import:LIPO-1100")
      (libsource (lib "eagle-import") (part "LIPO-OUTLINE1100"))
    )
    (comp (ref "U4")
      (value "BQ24022")
      (footprint "eagle-import:DRC-10")
      (libsource (lib "eagle-import") (part "BQ24022"))
    )
    (comp (ref "D9")
      (value "BLUE")
      (footprint "eagle-import:LED-0603")
      (libsource (lib "eagle-import") (part "LED-BLUE0603"))
    )
    (comp (ref "D10")
      (value "BLUE")
      (footprint "eagle-import:LED-0603")
      (libsource (lib "eagle-import") (part "LED-BLUE0603"))
    )
    (comp (ref "R20")
      (value "200")
      (footprint "eagle-import:0603-RES")
      (libsource (lib "eagle-import") (part "RESISTOR0603-RES"))
    )
    (comp (ref "R21")
      (value "200")
      (footprint "eagle-import:0603-RES")
      (libsource (lib "eagle-import") (part "RESISTOR0603-RES"))
    )
    (comp (ref "U$4")
      (value "WS_CORE51822")
      (footprint "eagle-import:WS_CORE51822")
      (libsource (lib "eagle-import") (part "WS_CORE51822"))
    )
    (comp (ref "U$15")
      (value "2X5_0.05\"_CORTEX_DEBUGTH_NOKEY_UNSHROUDED")
      (footprint "eagle-import:2X5_0.05__TH_NS")
      (libsource (lib "eagle-import") (part "2X5_0.05{dblquote}_CORTEX_DEBUGTH_NOKEY_UNSHROUDED"))
    )
  )
  (nets
    (net (code "1") (name "ACCEL_CS") (class "Default")
      (node (ref "JP13") (pin "4") (pinfunction "4_4") (pintype "passive"))
      (node (ref "U$3") (pin "33") (pinfunction "PC4_33") (pintype "bidirectional"))
      (node (ref "U1") (pin "P$8") (pinfunction "~{CS}_P$8") (pintype "bidirectional"))
    )
    (net (code "2") (name "ACCEL_INT1") (class "Default")
      (node (ref "JP13") (pin "5") (pinfunction "5_5") (pintype "passive"))
      (node (ref "U$3") (pin "34") (pinfunction "PC5_34") (pintype "bidirectional"))
      (node (ref "U1") (pin "P$11") (pinfunction "INT1_P$11") (pintype "bidirectional"))
    )
    (net (code "3") (name "ACCEL_INT2") (class "Default")
      (node (ref "JP13") (pin "6") (pinfunction "6_6") (pintype "passive"))
      (node (ref "U$3") (pin "35") (pinfunction "PB0_35") (pintype "bidirectional"))
      (node (ref "U1") (pin "P$9") (pinfunction "INT2_P$9") (pintype "bidirectional"))
    )
    (net (code "4") (name "ACCEL_MISO") (class "Default")
      (node (ref "JP13") (pin "3") (pinfunction "3_3") (pintype "passive"))
      (node (ref "U$3") (pin "31") (pinfunction "PA6_31") (pintype "bidirectional"))
      (node (ref "U1") (pin "P$7") (pinfunction "MISO_P$7") (pintype "bidirectional"))
    )
    (net (code "5") (name "ACCEL_MOSI") (class "Default")
      (node (ref "JP13") (pin "2") (pinfunction "2_2") (pintype "passive"))
      (node (ref "U$3") (pin "32") (pinfunction "PA7_32") (pintype "bidirectional"))
      (node (ref "U1") (pin "P$6") (pinfunction "MOSI_P$6") (pintype "bidirectional"))
    )
    (net (code "6") (name "ACCEL_SCK") (class "Default")
      (node (ref "JP13") (pin "1") (pinfunction "1_1") (pintype "passive"))
      (node (ref "U$3") (pin "30") (pinfunction "PA5_30") (pintype "bidirectional"))
      (node (ref "U1") (pin "P$4") (pinfunction "SCLK_P$4") (pintype "bidirectional"))
    )
    (net (code "7") (name "BOOT_MODE") (class "Default")
      (node (ref "JP3") (pin "2") (pinfunction "2_2") (pintype "passive"))
      (node (ref "U$3") (pin "94") (pinfunction "BOOT0_94") (pintype "bidirectional"))
    )
    (net (code "8") (name "BTLE_CS") (class "Default")
      (node (ref "U$3") (pin "81") (pinfunction "PD0_81") (pintype "bidirectional"))
      (node (ref "U$4") (pin "P$5") (pinfunction "P0.24_P$5") (pintype "bidirectional"))
    )
    (net (code "9") (name "BTLE_CTS") (class "Default")
      (node (ref "U$3") (pin "73") (pinfunction "PF6_73") (pintype "bidirectional"))
      (node (ref "U$4") (pin "P$24") (pinfunction "P0.10_P$24") (pintype "bidirectional"))
    )
    (net (code "10") (name "BTLE_DFU") (class "Default")
      (node (ref "U$3") (pin "83") (pinfunction "PD2_83") (pintype "bidirectional"))
      (node (ref "U$4") (pin "P$21") (pinfunction "P0.07_P$21") (pintype "bidirectional"))
    )
    (net (code "11") (name "BTLE_FACTORY_RESET") (class "Default")
      (node (ref "U$3") (pin "84") (pinfunction "PD3_84") (pintype "bidirectional"))
      (node (ref "U$4") (pin "P$30") (pinfunction "P0.16_P$30") (pintype "bidirectional"))
    )
    (net (code "12") (name "BTLE_INT") (class "Default")
      (node (ref "U$3") (pin "82") (pinfunction "PD1_82") (pintype "bidirectional"))
      (node (ref "U$4") (pin "P$6") (pinfunction "P0.25_P$6") (pintype "bidirectional"))
    )
    (net (code "13") (name "BTLE_MISO") (class "Default")
      (node (ref "U$3") (pin "79") (pinfunction "PC11_79") (pintype "bidirectional"))
      (node (ref "U$4") (pin "P$3") (pinfunction "P0.22_P$3") (pintype "bidirectional"))
    )
    (net (code "14") (name "BTLE_MODE") (class "Default")
      (node (ref "U$3") (pin "97") (pinfunction "PE0_97") (pintype "bidirectional"))
      (node (ref "U$4") (pin "P$15") (pinfunction "P0.01_P$15") (pintype "bidirectional"))
    )
    (net (code "15") (name "BTLE_MOSI") (class "Default")
      (node (ref "U$3") (pin "80") (pinfunction "PC12_80") (pintype "bidirectional"))
      (node (ref "U$4") (pin "P$4") (pinfunction "P0.23_P$4") (pintype "bidirectional"))
    )
    (net (code "16") (name "BTLE_POWER") (class "Default")
      (node (ref "C17") (pin "2") (pinfunction "C2_2") (pintype "passive"))
      (node (ref "U$17") (pin "3") (pinfunction "D_3") (pintype "passive"))
      (node (ref "U$4") (pin "P$11") (pinfunction "VDD_P$11") (pintype "bidirectional"))
    )
    (net (code "17") (name "BTLE_POWER_EN") (class "Default")
      (node (ref "U$17") (pin "1") (pinfunction "G_1") (pintype "passive"))
      (node (ref "U$3") (pin "85") (pinfunction "PD4_85") (pintype "bidirectional"))
    )
    (net (code "18") (name "BTLE_RTS") (class "Default")
      (node (ref "U$3") (pin "58") (pinfunction "PD11_58") (pintype "bidirectional"))
      (node (ref "U$4") (pin "P$22") (pinfunction "P0.08_P$22") (pintype "bidirectional"))
    )
    (net (code "19") (name "BTLE_RXD") (class "Default")
      (node (ref "U$3") (pin "96") (pinfunction "PB9_96") (pintype "bidirectional"))
      (node (ref "U$4") (pin "P$25") (pinfunction "P0.11_P$25") (pintype "bidirectional"))
    )
    (net (code "20") (name "BTLE_SCK") (class "Default")
      (node (ref "U$3") (pin "78") (pinfunction "PC10_78") (pintype "bidirectional"))
      (node (ref "U$4") (pin "P$2") (pinfunction "P0.21_P$2") (pintype "bidirectional"))
    )
    (net (code "21") (name "BTLE_TX") (class "Default")
      (node (ref "U$3") (pin "95") (pinfunction "PB8_95") (pintype "bidirectional"))
      (node (ref "U$4") (pin "P$23") (pinfunction "P0.09_P$23") (pintype "bidirectional"))
    )
    (net (code "22") (name "BUTTON_EXTERNAL") (class "Default")
      (node (ref "C11") (pin "1") (pinfunction "1_1") (pintype "passive"))
      (node (ref "JP12") (pin "1") (pinfunction "1_1") (pintype "passive"))
      (node (ref "U$3") (pin "91") (pinfunction "PB5_91") (pintype "bidirectional"))
    )
    (net (code "23") (name "BUTTON_PCB") (class "Default")
      (node (ref "C10") (pin "1") (pinfunction "1_1") (pintype "passive"))
      (node (ref "S2") (pin "3") (pinfunction "2_3") (pintype "passive"))
      (node (ref "U$3") (pin "92") (pinfunction "PB6_92") (pintype "bidirectional"))
    )
    (net (code "24") (name "CHARGER_CE") (class "Default")
      (node (ref "R31") (pin "2") (pinfunction "2_2") (pintype "passive"))
      (node (ref "U$3") (pin "64") (pinfunction "PC7_64") (pintype "bidirectional"))
    )
    (net (code "25") (name "CHARGER_ISET2") (class "Default")
      (node (ref "R36") (pin "2") (pinfunction "2_2") (pintype "passive"))
      (node (ref "U$3") (pin "65") (pinfunction "PC8_65") (pintype "bidirectional"))
    )
    (net (code "26") (name "CHARGER_PGOOD") (class "Default")
      (node (ref "R29") (pin "2") (pinfunction "2_2") (pintype "passive"))
      (node (ref "U$3") (pin "63") (pinfunction "PC6_63") (pintype "bidirectional"))
    )
    (net (code "27") (name "CHARGER_STAT1") (class "Default")
      (node (ref "R26") (pin "2") (pinfunction "2_2") (pintype "passive"))
      (node (ref "U$3") (pin "67") (pinfunction "PA8_67") (pintype "bidirectional"))
    )
    (net (code "28") (name "CHARGER_STAT2") (class "Default")
      (node (ref "R27") (pin "2") (pinfunction "2_2") (pintype "passive"))
      (node (ref "U$3") (pin "66") (pinfunction "PC9_66") (pintype "bidirectional"))
    )
    (net (code "29") (name "CONNECTED_LED") (class "Default")
      (node (ref "D9") (pin "A") (pinfunction "A_A") (pintype "passive"))
      (node (ref "U$4") (pin "P$34") (pinfunction "P0.19_P$34") (pintype "bidirectional"))
    )
    (net (code "30") (name "CONSOLE_RX") (class "Default")
      (node (ref "R3") (pin "1") (pinfunction "1_1") (pintype "passive"))
      (node (ref "U$3") (pin "69") (pinfunction "PA10_69") (pintype "bidirectional"))
    )
    (net (code "31") (name "CONSOLE_TX") (class "Default")
      (node (ref "R2") (pin "1") (pinfunction "1_1") (pintype "passive"))
      (node (ref "U$3") (pin "68") (pinfunction "PA9_68") (pintype "bidirectional"))
    )
    (net (code "32") (name "DEBUG_GNDDETECT") (class "Default")
      (node (ref "U$3") (pin "88") (pinfunction "PD7_88") (pintype "bidirectional"))
    )
    (net (code "33") (name "DEBUG_JTDI") (class "Default")
      (node (ref "R40") (pin "2") (pinfunction "2_2") (pintype "passive"))
      (node (ref "U$12") (pin "5") (pinfunction "NC/TDI_5") (pintype "bidirectional"))
      (node (ref "U$2") (pin "8") (pinfunction "NC/EXTB/TDI_8") (pintype "bidirectional"))
      (node (ref "U$3") (pin "77") (pinfunction "PA15_77") (pintype "bidirectional"))
    )
    (net (code "34") (name "DEBUG_JTDO_TRACESWO") (class "Default")
      (node (ref "U$12") (pin "13") (pinfunction "SWO/TDO_13") (pintype "bidirectional"))
      (node (ref "U$2") (pin "6") (pinfunction "SWO/TDO/EXTA/TRACECTL_6") (pintype "bidirectional"))
      (node (ref "U$3") (pin "89") (pinfunction "PB3_89") (pintype "bidirectional"))
    )
    (net (code "35") (name "DEBUG_SWCLK_JTCK") (class "Default")
      (node (ref "R43") (pin "2") (pinfunction "2_2") (pintype "passive"))
      (node (ref "U$12") (pin "9") (pinfunction "SWCLK/TCLK_9") (pintype "bidirectional"))
      (node (ref "U$2") (pin "4") (pinfunction "SWDCLK/TCK_4") (pintype "bidirectional"))
      (node (ref "U$3") (pin "76") (pinfunction "PA14_76") (pintype "bidirectional"))
    )
    (net (code "36") (name "DEBUG_SWDIO_JTMS") (class "Default")
      (node (ref "R41") (pin "2") (pinfunction "2_2") (pintype "passive"))
      (node (ref "U$12") (pin "7") (pinfunction "SWDIO/TMS_7") (pintype "bidirectional"))
      (node (ref "U$2") (pin "2") (pinfunction "SWDIO/TMS_2") (pintype "bidirectional"))
      (node (ref "U$3") (pin "72") (pinfunction "PA13_72") (pintype "bidirectional"))
    )
    (net (code "37") (name "DEBUG_TRACECLK") (class "Default")
      (node (ref "U$2") (pin "12") (pinfunction "TRACECLK_12") (pintype "bidirectional"))
      (node (ref "U$3") (pin "1") (pinfunction "PE2_1") (pintype "bidirectional"))
    )
    (net (code "38") (name "DEBUG_TRACE_D0") (class "Default")
      (node (ref "U$2") (pin "14") (pinfunction "TRACEDATA[0]_14") (pintype "bidirectional"))
      (node (ref "U$3") (pin "2") (pinfunction "PE3_2") (pintype "bidirectional"))
    )
    (net (code "39") (name "DEBUG_TRACE_D1") (class "Default")
      (node (ref "U$2") (pin "16") (pinfunction "TRACEDATA[1]_16") (pintype "bidirectional"))
      (node (ref "U$3") (pin "3") (pinfunction "PE4_3") (pintype "bidirectional"))
    )
    (net (code "40") (name "DEBUG_TRACE_D2") (class "Default")
      (node (ref "U$2") (pin "18") (pinfunction "TRACEDATA[2]_18") (pintype "bidirectional"))
      (node (ref "U$3") (pin "4") (pinfunction "PE5_4") (pintype "bidirectional"))
    )
    (net (code "41") (name "DEBUG_TRACE_D3") (class "Default")
      (node (ref "U$2") (pin "20") (pinfunction "TRACEDATA[3]_20") (pintype "bidirectional"))
      (node (ref "U$3") (pin "5") (pinfunction "PE6_5") (pintype "bidirectional"))
    )
    (net (code "42") (name "DEBUG_TRST") (class "Default")
      (node (ref "R42") (pin "2") (pinfunction "2_2") (pintype "passive"))
      (node (ref "U$12") (pin "3") (pinfunction "TRST_3") (pintype "bidirectional"))
      (node (ref "U$3") (pin "90") (pinfunction "PB4_90") (pintype "bidirectional"))
    )
    (net (code "43") (name "FLASH_CS") (class "Default")
      (node (ref "JP14") (pin "7") (pinfunction "7_7") (pintype "passive"))
      (node (ref "U$11") (pin "P$1") (pinfunction "CS_P$1") (pintype "bidirectional"))
      (node (ref "U$3") (pin "40") (pinfunction "PE9_40") (pintype "bidirectional"))
    )
    (net (code "44") (name "FLASH_HOLD") (class "Default")
      (node (ref "JP14") (pin "9") (pinfunction "9_9") (pintype "passive"))
      (node (ref "U$11") (pin "P$7") (pinfunction "HOLD_P$7") (pintype "bidirectional"))
      (node (ref "U$3") (pin "39") (pinfunction "PE8_39") (pintype "bidirectional"))
    )
    (net (code "45") (name "FLASH_POWER") (class "Default")
      (node (ref "C19") (pin "2") (pinfunction "C2_2") (pintype "passive"))
      (node (ref "TP2") (pin "TP") (pinfunction "TP_TP") (pintype "input"))
      (node (ref "U$11") (pin "P$8") (pinfunction "VCC_P$8") (pintype "bidirectional"))
      (node (ref "U$19") (pin "3") (pinfunction "D_3") (pintype "passive"))
    )
    (net (code "46") (name "FLASH_POWER_EN") (class "Default")
      (node (ref "U$19") (pin "1") (pinfunction "G_1") (pintype "passive"))
      (node (ref "U$3") (pin "37") (pinfunction "PB2_37") (pintype "bidirectional"))
    )
    (net (code "47") (name "FLASH_WP") (class "Default")
      (node (ref "JP14") (pin "8") (pinfunction "8_8") (pintype "passive"))
      (node (ref "U$11") (pin "P$3") (pinfunction "WP_P$3") (pintype "bidirectional"))
      (node (ref "U$3") (pin "38") (pinfunction "PE7_38") (pintype "bidirectional"))
    )
    (net (code "48") (name "GND") (class "Default")
      (node (ref "BAT4") (pin "GND") (pinfunction "-_GND") (pintype "power_in"))
      (node (ref "C1") (pin "2") (pinfunction "2_2") (pintype "passive"))
      (node (ref "C10") (pin "2") (pinfunction "2_2") (pintype "passive"))
      (node (ref "C11") (pin "2") (pinfunction "2_2") (pintype "passive"))
      (node (ref "C12") (pin "2") (pinfunction "2_2") (pintype "passive"))
      (node (ref "C13") (pin "2") (pinfunction "2_2") (pintype "passive"))
      (node (ref "C14") (pin "2") (pinfunction "C2_2") (pintype "passive"))
      (node (ref "C15") (pin "2") (pinfunction "C2_2") (pintype "passive"))
      (node (ref "C16") (pin "1") (pinfunction "C1_1") (pintype "passive"))
      (node (ref "C17") (pin "1") (pinfunction "C1_1") (pintype "passive"))
      (node (ref "C18") (pin "1") (pinfunction "C1_1") (pintype "passive"))
      (node (ref "C19") (pin "1") (pinfunction "C1_1") (pintype "passive"))
      (node (ref "C2") (pin "2") (pinfunction "2_2") (pintype "passive"))
      (node (ref "C20") (pin "1") (pinfunction "C1_1") (pintype "passive"))
      (node (ref "C3") (pin "2") (pinfunction "C2_2") (pintype "passive"))
      (node (ref "C4") (pin "1") (pinfunction "C1_1") (pintype "passive"))
      (node (ref "C5") (pin "1") (pinfunction "C1_1") (pintype "passive"))
      (node (ref "C6") (pin "1") (pinfunction "C1_1") (pintype "passive"))
      (node (ref "C7") (pin "2") (pinfunction "C2_2") (pintype "passive"))
      (node (ref "C8") (pin "2") (pinfunction "2_2") (pintype "passive"))
      (node (ref "C9") (pin "2") (pinfunction "C2_2") (pintype "passive"))
      (node (ref "CN2") (pin "2") (pinfunction "1_2") (pintype "passive"))
      (node (ref "JP12") (pin "2") (pinfunction "2_2") (pintype "passive"))
      (node (ref "JP13") (pin "7") (pinfunction "7_7") (pintype "passive"))
      (node (ref "JP14") (pin "10") (pinfunction "10_10") (pintype "passive"))
      (node (ref "JP17") (pin "3") (pinfunction "3_3") (pintype "passive"))
      (node (ref "JP4") (pin "4") (pinfunction "4_4") (pintype "passive"))
      (node (ref "R1") (pin "1") (pinfunction "1_1") (pintype "passive"))
      (node (ref "R20") (pin "1") (pinfunction "1_1") (pintype "passive"))
      (node (ref "R21") (pin "1") (pinfunction "1_1") (pintype "passive"))
      (node (ref "R30") (pin "1") (pinfunction "1_1") (pintype "passive"))
      (node (ref "R32") (pin "1") (pinfunction "1_1") (pintype "passive"))
      (node (ref "R37") (pin "2") (pinfunction "2_2") (pintype "passive"))
      (node (ref "R7") (pin "1") (pinfunction "1_1") (pintype "passive"))
      (node (ref "S2") (pin "1") (pinfunction "1_1") (pintype "passive"))
      (node (ref "S3") (pin "1") (pinfunction "1_1") (pintype "passive"))
      (node (ref "S4") (pin "6") (pinfunction "6_6") (pintype "bidirectional"))
      (node (ref "T1") (pin "2") (pinfunction "E_2") (pintype "passive"))
      (node (ref "U$1") (pin "P$2") (pinfunction "GND_P$2") (pintype "bidirectional"))
      (node (ref "U$1") (pin "P$7") (pinfunction "REF_P$7") (pintype "bidirectional"))
      (node (ref "U$10") (pin "P$13") (pinfunction "RF_GND_P$13") (pintype "bidirectional"))
      (node (ref "U$10") (pin "P$21") (pinfunction "GND_P$21") (pintype "bidirectional"))
      (node (ref "U$11") (pin "P$4") (pinfunction "VSS_P$4") (pintype "bidirectional"))
      (node (ref "U$11") (pin "P$9") (pinfunction "CENTER_PAD_P$9") (pintype "bidirectional"))
      (node (ref "U$12") (pin "10") (pinfunction "GND_10") (pintype "bidirectional"))
      (node (ref "U$12") (pin "11") (pinfunction "RTCK_11") (pintype "bidirectional"))
      (node (ref "U$12") (pin "12") (pinfunction "GND_12") (pintype "bidirectional"))
      (node (ref "U$12") (pin "14") (pinfunction "GND_14") (pintype "bidirectional"))
      (node (ref "U$12") (pin "16") (pinfunction "GND_16") (pintype "bidirectional"))
      (node (ref "U$12") (pin "18") (pinfunction "GND_18") (pintype "bidirectional"))
      (node (ref "U$12") (pin "20") (pinfunction "GND_20") (pintype "bidirectional"))
      (node (ref "U$12") (pin "4") (pinfunction "GND_4") (pintype "bidirectional"))
      (node (ref "U$12") (pin "6") (pinfunction "GND_6") (pintype "bidirectional"))
      (node (ref "U$12") (pin "8") (pinfunction "GND_8") (pintype "bidirectional"))
      (node (ref "U$15") (pin "3") (pinfunction "GND_3") (pintype "bidirectional"))
      (node (ref "U$15") (pin "5") (pinfunction "GND_5") (pintype "bidirectional"))
      (node (ref "U$2") (pin "11") (pinfunction "GND/TGTPWR+CAP_11") (pintype "bidirectional"))
      (node (ref "U$2") (pin "13") (pinfunction "GND/TGTPWR+CAP_13") (pintype "bidirectional"))
      (node (ref "U$2") (pin "15") (pinfunction "GND_15") (pintype "bidirectional"))
      (node (ref "U$2") (pin "17") (pinfunction "GND_17") (pintype "bidirectional"))
      (node (ref "U$2") (pin "19") (pinfunction "GND_19") (pintype "bidirectional"))
      (node (ref "U$2") (pin "3") (pinfunction "GND_3") (pintype "bidirectional"))
      (node (ref "U$2") (pin "5") (pinfunction "GND_5") (pintype "bidirectional"))
      (node (ref "U$2") (pin "9") (pinfunction "GND_DETECT_9") (pintype "bidirectional"))
      (node (ref "U$3") (pin "20") (pinfunction "VSSA_VREF-_20") (pintype "bidirectional"))
      (node (ref "U$3") (pin "27") (pinfunction "PF4_27") (pintype "bidirectional"))
      (node (ref "U$3") (pin "49") (pinfunction "VSS_1_49") (pintype "bidirectional"))
      (node (ref "U$3") (pin "74") (pinfunction "VSS_2_74") (pintype "bidirectional"))
      (node (ref "U$3") (pin "99") (pinfunction "VSS_3_99") (pintype "bidirectional"))
      (node (ref "U$4") (pin "P$1") (pinfunction "GND0_P$1") (pintype "bidirectional"))
      (node (ref "U$4") (pin "P$12") (pinfunction "GND1_P$12") (pintype "bidirectional"))
      (node (ref "U$6") (pin "P$5") (pinfunction "GND_P$5") (pintype "bidirectional"))
      (node (ref "U$6") (pin "P$6") (pinfunction "SHIELD1_P$6") (pintype "bidirectional"))
      (node (ref "U$6") (pin "P$7") (pinfunction "SHIELD2_P$7") (pintype "bidirectional"))
      (node (ref "U1") (pin "P$12") (pinfunction "GND_P$12") (pintype "bidirectional"))
      (node (ref "U1") (pin "P$13") (pinfunction "GND_P$13") (pintype "bidirectional"))
      (node (ref "U1") (pin "P$16") (pinfunction "GND_P$16") (pintype "bidirectional"))
      (node (ref "U2") (pin "2") (pinfunction "GND_2") (pintype "input"))
      (node (ref "U2") (pin "4") (pinfunction "GND_4") (pintype "input"))
      (node (ref "U3") (pin "GND") (pinfunction "GND_GND") (pintype "bidirectional"))
      (node (ref "U3") (pin "GND1") (pinfunction "SHIELD_GND1") (pintype "bidirectional"))
      (node (ref "U3") (pin "GND3") (pinfunction "SHIELD_GND3") (pintype "bidirectional"))
      (node (ref "U4") (pin "5") (pinfunction "GND_5") (pintype "bidirectional"))
      (node (ref "U4") (pin "EP") (pinfunction "ETP_EP") (pintype "bidirectional"))
    )
    (net (code "49") (name "GPS_HS_CLK") (class "Default")
      (node (ref "JP4") (pin "2") (pinfunction "2_2") (pintype "passive"))
      (node (ref "U$10") (pin "P$17") (pinfunction "GPIO12_P$17") (pintype "bidirectional"))
      (node (ref "U$3") (pin "43") (pinfunction "PE12_43") (pintype "bidirectional"))
    )
    (net (code "50") (name "GPS_HS_SIGN") (class "Default")
      (node (ref "JP4") (pin "1") (pinfunction "1_1") (pintype "passive"))
      (node (ref "U$10") (pin "P$18") (pinfunction "GPIO13_P$18") (pintype "bidirectional"))
      (node (ref "U$3") (pin "44") (pinfunction "PE13_44") (pintype "bidirectional"))
    )
    (net (code "51") (name "GPS_HS_SS") (class "Default")
      (node (ref "JP4") (pin "3") (pinfunction "3_3") (pintype "passive"))
      (node (ref "U$10") (pin "P$11") (pinfunction "GPIO16_P$11") (pintype "bidirectional"))
      (node (ref "U$3") (pin "42") (pinfunction "PE11_42") (pintype "bidirectional"))
    )
    (net (code "52") (name "GPS_NMEA_TX") (class "Default")
      (node (ref "U$10") (pin "P$12") (pinfunction "TXD1_P$12") (pintype "bidirectional"))
      (node (ref "U$3") (pin "26") (pinfunction "PA3_26") (pintype "bidirectional"))
    )
    (net (code "53") (name "GPS_POWER") (class "Default")
      (node (ref "C18") (pin "2") (pinfunction "C2_2") (pintype "passive"))
      (node (ref "U$10") (pin "P$24") (pinfunction "BATTERY_P$24") (pintype "bidirectional"))
      (node (ref "U$18") (pin "3") (pinfunction "D_3") (pintype "passive"))
    )
    (net (code "54") (name "GPS_POWER_EN") (class "Default")
      (node (ref "U$18") (pin "1") (pinfunction "G_1") (pintype "passive"))
      (node (ref "U$3") (pin "48") (pinfunction "PB11_48") (pintype "bidirectional"))
    )
    (net (code "55") (name "GPS_PROG_RX") (class "Default")
      (node (ref "U$10") (pin "P$1") (pinfunction "RXD2_P$1") (pintype "bidirectional"))
      (node (ref "U$3") (pin "47") (pinfunction "PB10_47") (pintype "bidirectional"))
    )
    (net (code "56") (name "GPS_PROG_TX") (class "Default")
      (node (ref "U$10") (pin "P$2") (pinfunction "TXD2_P$2") (pintype "bidirectional"))
      (node (ref "U$3") (pin "46") (pinfunction "PE15_46") (pintype "bidirectional"))
    )
    (net (code "57") (name "GPS_SECOND") (class "Default")
      (node (ref "U$10") (pin "P$3") (pinfunction "P1PPS_P$3") (pintype "bidirectional"))
      (node (ref "U$3") (pin "36") (pinfunction "PB1_36") (pintype "bidirectional"))
    )
    (net (code "58") (name "GPS_TRIG_TIMESTAMP") (class "Default")
      (node (ref "U$10") (pin "P$15") (pinfunction "TRIG_P$15") (pintype "bidirectional"))
      (node (ref "U$3") (pin "45") (pinfunction "PE14_45") (pintype "bidirectional"))
    )
    (net (code "59") (name "IMEAS_GAIN0_OUT") (class "Default")
      (node (ref "U$1") (pin "P$5") (pinfunction "GS0_P$5") (pintype "bidirectional"))
      (node (ref "U$3") (pin "61") (pinfunction "PD14_61") (pintype "bidirectional"))
    )
    (net (code "60") (name "IMEAS_GAIN1_OUT") (class "Default")
      (node (ref "U$1") (pin "P$6") (pinfunction "GS1_P$6") (pintype "bidirectional"))
      (node (ref "U$3") (pin "62") (pinfunction "PD15_62") (pintype "bidirectional"))
    )
    (net (code "61") (name "IMEAS_IN+") (class "Default")
      (node (ref "TP6") (pin "TP") (pinfunction "TP_TP") (pintype "input"))
      (node (ref "U$1") (pin "P$4") (pinfunction "OUT_P$4") (pintype "bidirectional"))
      (node (ref "U$3") (pin "60") (pinfunction "PD13_60") (pintype "bidirectional"))
    )
    (net (code "62") (name "LED_OUT0") (class "Default")
      (node (ref "D1") (pin "A") (pinfunction "A_A") (pintype "passive"))
      (node (ref "U$3") (pin "93") (pinfunction "PB7_93") (pintype "bidirectional"))
    )
    (net (code "63") (name "MODE_LED") (class "Default")
      (node (ref "D10") (pin "A") (pinfunction "A_A") (pintype "passive"))
      (node (ref "U$4") (pin "P$33") (pinfunction "P0.17_P$33") (pintype "bidirectional"))
    )
    (net (code "64") (name "NRST") (class "Default")
      (node (ref "C8") (pin "1") (pinfunction "1_1") (pintype "passive"))
      (node (ref "S3") (pin "3") (pinfunction "2_3") (pintype "passive"))
      (node (ref "U$12") (pin "15") (pinfunction "~{RESET}_15") (pintype "bidirectional"))
      (node (ref "U$2") (pin "10") (pinfunction "~{RESET}_10") (pintype "bidirectional"))
      (node (ref "U$3") (pin "14") (pinfunction "NRST_14") (pintype "bidirectional"))
    )
    (net (code "65") (name "Net-(C3-C1)") (class "Default")
      (node (ref "C3") (pin "1") (pinfunction "C1_1") (pintype "passive"))
      (node (ref "R8") (pin "1") (pinfunction "1_1") (pintype "passive"))
      (node (ref "SJ1") (pin "2") (pinfunction "2_2") (pintype "passive"))
      (node (ref "U$1") (pin "P$1") (pinfunction "IN+_P$1") (pintype "bidirectional"))
      (node (ref "U2") (pin "5") (pinfunction "VCC_5") (pintype "power_in"))
    )
    (net (code "66") (name "Net-(D1-PadC)") (class "Default")
      (node (ref "D1") (pin "C") (pinfunction "C_C") (pintype "passive"))
      (node (ref "R1") (pin "2") (pinfunction "2_2") (pintype "passive"))
    )
    (net (code "67") (name "Net-(D4-PadA)") (class "Default")
      (node (ref "D4") (pin "A") (pinfunction "A_A") (pintype "passive"))
      (node (ref "R18") (pin "1") (pinfunction "1_1") (pintype "passive"))
    )
    (net (code "68") (name "Net-(D5-PadA)") (class "Default")
      (node (ref "D5") (pin "A") (pinfunction "A_A") (pintype "passive"))
      (node (ref "R19") (pin "1") (pinfunction "1_1") (pintype "passive"))
    )
    (net (code "69") (name "Net-(D6-PadA)") (class "Default")
      (node (ref "D6") (pin "A") (pinfunction "A_A") (pintype "passive"))
      (node (ref "R28") (pin "1") (pinfunction "1_1") (pintype "passive"))
    )
    (net (code "70") (name "Net-(D9-PadC)") (class "Default")
      (node (ref "D9") (pin "C") (pinfunction "C_C") (pintype "passive"))
      (node (ref "R20") (pin "2") (pinfunction "2_2") (pintype "passive"))
    )
    (net (code "71") (name "Net-(D10-PadC)") (class "Default")
      (node (ref "D10") (pin "C") (pinfunction "C_C") (pintype "passive"))
      (node (ref "R21") (pin "2") (pinfunction "2_2") (pintype "passive"))
    )
    (net (code "72") (name "Net-(D11-PadC)") (class "Default")
      (node (ref "D11") (pin "C") (pinfunction "C_C") (pintype "passive"))
      (node (ref "R9") (pin "1") (pinfunction "1_1") (pintype "passive"))
      (node (ref "S4") (pin "5") (pinfunction "5_5") (pintype "bidirectional"))
    )
    (net (code "73") (name "Net-(JP17-Pad1)") (class "Default")
      (node (ref "JP17") (pin "1") (pinfunction "1_1") (pintype "passive"))
      (node (ref "R2") (pin "2") (pinfunction "2_2") (pintype "passive"))
    )
    (net (code "74") (name "Net-(JP17-Pad2)") (class "Default")
      (node (ref "JP17") (pin "2") (pinfunction "2_2") (pintype "passive"))
      (node (ref "R3") (pin "2") (pinfunction "2_2") (pintype "passive"))
    )
    (net (code "75") (name "Net-(T1-B)") (class "Default")
      (node (ref "R5") (pin "1") (pinfunction "1_1") (pintype "passive"))
      (node (ref "T1") (pin "1") (pinfunction "B_1") (pintype "passive"))
    )
    (net (code "76") (name "Net-(T1-C)") (class "Default")
      (node (ref "R4") (pin "1") (pinfunction "1_1") (pintype "passive"))
      (node (ref "T1") (pin "3") (pinfunction "C_3") (pintype "passive"))
      (node (ref "U$5") (pin "1") (pinfunction "G_1") (pintype "passive"))
    )
    (net (code "77") (name "Net-(U$1-VS)") (class "Default")
      (node (ref "SJ3") (pin "2") (pinfunction "2_2") (pintype "passive"))
      (node (ref "U$1") (pin "P$3") (pinfunction "VS_P$3") (pintype "bidirectional"))
    )
    (net (code "78") (name "Net-(U$5-D)") (class "Default")
      (node (ref "R6") (pin "2") (pinfunction "2_2") (pintype "passive"))
      (node (ref "U$5") (pin "3") (pinfunction "D_3") (pintype "passive"))
    )
    (net (code "79") (name "Net-(U$6-D+)") (class "Default")
      (node (ref "R34") (pin "1") (pinfunction "1_1") (pintype "passive"))
      (node (ref "R35") (pin "1") (pinfunction "1_1") (pintype "passive"))
      (node (ref "U$6") (pin "P$3") (pinfunction "D+_P$3") (pintype "bidirectional"))
    )
    (net (code "80") (name "Net-(U$6-D-)") (class "Default")
      (node (ref "R33") (pin "1") (pinfunction "1_1") (pintype "passive"))
      (node (ref "U$6") (pin "P$2") (pinfunction "D-_P$2") (pintype "bidirectional"))
    )
    (net (code "81") (name "Net-(U$6-ID)") (class "Default")
      (node (ref "R37") (pin "1") (pinfunction "1_1") (pintype "passive"))
      (node (ref "U$6") (pin "P$4") (pinfunction "ID_P$4") (pintype "bidirectional"))
    )
    (net (code "82") (name "Net-(U1-VDDIO)") (class "Default")
      (node (ref "SJ2") (pin "2") (pinfunction "2_2") (pintype "passive"))
      (node (ref "U1") (pin "P$1") (pinfunction "VDDIO_P$1") (pintype "bidirectional"))
      (node (ref "U1") (pin "P$14") (pinfunction "VS_P$14") (pintype "bidirectional"))
    )
    (net (code "83") (name "Net-(U4-ISET1)") (class "Default")
      (node (ref "R30") (pin "2") (pinfunction "2_2") (pintype "passive"))
      (node (ref "U4") (pin "6") (pinfunction "ISET1_6") (pintype "bidirectional"))
    )
    (net (code "84") (name "Net-(U4-ISET2)") (class "Default")
      (node (ref "R36") (pin "1") (pinfunction "1_1") (pintype "passive"))
      (node (ref "U4") (pin "7") (pinfunction "ISET2_7") (pintype "bidirectional"))
    )
    (net (code "85") (name "Net-(U4-STAT1)") (class "Default")
      (node (ref "D5") (pin "C") (pinfunction "C_C") (pintype "passive"))
      (node (ref "R26") (pin "1") (pinfunction "1_1") (pintype "passive"))
      (node (ref "U4") (pin "3") (pinfunction "STAT1_3") (pintype "bidirectional"))
    )
    (net (code "86") (name "Net-(U4-STAT2)") (class "Default")
      (node (ref "D4") (pin "C") (pinfunction "C_C") (pintype "passive"))
      (node (ref "R27") (pin "1") (pinfunction "1_1") (pintype "passive"))
      (node (ref "U4") (pin "4") (pinfunction "STAT2_4") (pintype "bidirectional"))
    )
    (net (code "87") (name "Net-(U4-~{CE})") (class "Default")
      (node (ref "R31") (pin "1") (pinfunction "1_1") (pintype "passive"))
      (node (ref "R32") (pin "2") (pinfunction "2_2") (pintype "passive"))
      (node (ref "U4") (pin "9") (pinfunction "~{CE}_9") (pintype "bidirectional"))
    )
    (net (code "88") (name "Net-(U4-~{PG})") (class "Default")
      (node (ref "D6") (pin "C") (pinfunction "C_C") (pintype "passive"))
      (node (ref "R29") (pin "1") (pinfunction "1_1") (pintype "passive"))
      (node (ref "U4") (pin "8") (pinfunction "~{PG}_8") (pintype "bidirectional"))
    )
    (net (code "89") (name "RCC_OSC32_IN") (class "Default")
      (node (ref "C1") (pin "1") (pinfunction "1_1") (pintype "passive"))
      (node (ref "Q1") (pin "1") (pinfunction "1_1") (pintype "passive"))
      (node (ref "U$3") (pin "8") (pinfunction "PC14_OSC32_IN_8") (pintype "bidirectional"))
    )
    (net (code "90") (name "RCC_OSC32_OUT") (class "Default")
      (node (ref "C2") (pin "1") (pinfunction "1_1") (pintype "passive"))
      (node (ref "Q1") (pin "4") (pinfunction "2_4") (pintype "passive"))
      (node (ref "U$3") (pin "9") (pinfunction "PC15_OSC32_OUT_9") (pintype "bidirectional"))
    )
    (net (code "91") (name "RCC_OSC_IN") (class "Default")
      (node (ref "C12") (pin "1") (pinfunction "1_1") (pintype "passive"))
      (node (ref "Q2") (pin "1") (pinfunction "1_1") (pintype "passive"))
      (node (ref "U$3") (pin "12") (pinfunction "PF0_OSC_IN_12") (pintype "bidirectional"))
    )
    (net (code "92") (name "RCC_OSC_OUT") (class "Default")
      (node (ref "C13") (pin "1") (pinfunction "1_1") (pintype "passive"))
      (node (ref "Q2") (pin "2") (pinfunction "2_2") (pintype "passive"))
      (node (ref "U$3") (pin "13") (pinfunction "PF1_OSC_OUT_13") (pintype "bidirectional"))
    )
    (net (code "93") (name "REG_EN") (class "Default")
      (node (ref "D8") (pin "C") (pinfunction "C_C") (pintype "passive"))
      (node (ref "R9") (pin "2") (pinfunction "2_2") (pintype "passive"))
      (node (ref "S4") (pin "2") (pinfunction "2_2") (pintype "bidirectional"))
      (node (ref "U2") (pin "3") (pinfunction "EN_3") (pintype "input"))
    )
    (net (code "94") (name "SDCARD_CS") (class "Default")
      (node (ref "JP14") (pin "1") (pinfunction "1_1") (pintype "passive"))
      (node (ref "U$3") (pin "51") (pinfunction "PB12_51") (pintype "bidirectional"))
      (node (ref "U3") (pin "CS") (pinfunction "CS_CS") (pintype "bidirectional"))
    )
    (net (code "95") (name "SDCARD_DETECT_IN") (class "Default")
      (node (ref "JP14") (pin "6") (pinfunction "6_6") (pintype "passive"))
      (node (ref "U$3") (pin "56") (pinfunction "PD9_56") (pintype "bidirectional"))
      (node (ref "U3") (pin "CD2") (pinfunction "CD2_CD2") (pintype "bidirectional"))
    )
    (net (code "96") (name "SDCARD_DETECT_OUT") (class "Default")
      (node (ref "JP14") (pin "5") (pinfunction "5_5") (pintype "passive"))
      (node (ref "U$3") (pin "55") (pinfunction "PD8_55") (pintype "bidirectional"))
      (node (ref "U3") (pin "CD1") (pinfunction "CD1_CD1") (pintype "bidirectional"))
    )
    (net (code "97") (name "SDCARD_MISO") (class "Default")
      (node (ref "JP14") (pin "3") (pinfunction "3_3") (pintype "passive"))
      (node (ref "U$11") (pin "P$2") (pinfunction "SO_P$2") (pintype "bidirectional"))
      (node (ref "U$3") (pin "53") (pinfunction "PB14_53") (pintype "bidirectional"))
      (node (ref "U3") (pin "DO") (pinfunction "DO_DO") (pintype "bidirectional"))
    )
    (net (code "98") (name "SDCARD_MOSI") (class "Default")
      (node (ref "JP14") (pin "2") (pinfunction "2_2") (pintype "passive"))
      (node (ref "U$11") (pin "P$5") (pinfunction "SI_P$5") (pintype "bidirectional"))
      (node (ref "U$3") (pin "54") (pinfunction "PB15_54") (pintype "bidirectional"))
      (node (ref "U3") (pin "DI") (pinfunction "DI_DI") (pintype "bidirectional"))
    )
    (net (code "99") (name "SDCARD_POWER_EN") (class "Default")
      (node (ref "U$13") (pin "1") (pinfunction "G_1") (pintype "passive"))
      (node (ref "U$3") (pin "57") (pinfunction "PD10_57") (pintype "bidirectional"))
    )
    (net (code "100") (name "SDCARD_SCK") (class "Default")
      (node (ref "JP14") (pin "4") (pinfunction "4_4") (pintype "passive"))
      (node (ref "U$11") (pin "P$6") (pinfunction "SCK_P$6") (pintype "bidirectional"))
      (node (ref "U$3") (pin "52") (pinfunction "PB13_52") (pintype "bidirectional"))
      (node (ref "U3") (pin "SCLK") (pinfunction "SCK_SCLK") (pintype "bidirectional"))
    )
    (net (code "101") (name "SD_POWER") (class "Default")
      (node (ref "C16") (pin "2") (pinfunction "C2_2") (pintype "passive"))
      (node (ref "TP1") (pin "TP") (pinfunction "TP_TP") (pintype "input"))
      (node (ref "U$13") (pin "3") (pinfunction "D_3") (pintype "passive"))
      (node (ref "U3") (pin "VCC") (pinfunction "VCC_VCC") (pintype "bidirectional"))
    )
    (net (code "102") (name "SWDCLK") (class "Default")
      (node (ref "U$15") (pin "4") (pinfunction "SWDCLK/TCK_4") (pintype "bidirectional"))
      (node (ref "U$4") (pin "P$32") (pinfunction "SWDCLK_P$32") (pintype "bidirectional"))
    )
    (net (code "103") (name "SWDIO") (class "Default")
      (node (ref "U$15") (pin "2") (pinfunction "SWDIO/TMS_2") (pintype "bidirectional"))
      (node (ref "U$4") (pin "P$31") (pinfunction "SWDIO_P$31") (pintype "bidirectional"))
    )
    (net (code "104") (name "SYSTEM_POWER_LATCH") (class "Default")
      (node (ref "D8") (pin "A") (pinfunction "A_A") (pintype "passive"))
      (node (ref "U$3") (pin "86") (pinfunction "PD5_86") (pintype "bidirectional"))
    )
    (net (code "105") (name "SYSTEM_POWER_SWITCH_STATE") (class "Default")
      (node (ref "D11") (pin "A") (pinfunction "A_A") (pintype "passive"))
      (node (ref "U$3") (pin "87") (pinfunction "PD6_87") (pintype "bidirectional"))
    )
    (net (code "106") (name "USB_DM") (class "Default")
      (node (ref "R33") (pin "2") (pinfunction "2_2") (pintype "passive"))
      (node (ref "U$3") (pin "70") (pinfunction "PA11_70") (pintype "bidirectional"))
    )
    (net (code "107") (name "USB_DP") (class "Default")
      (node (ref "R34") (pin "2") (pinfunction "2_2") (pintype "passive"))
      (node (ref "U$3") (pin "71") (pinfunction "PA12_71") (pintype "bidirectional"))
    )
    (net (code "108") (name "VBATT_BACKUP") (class "Default")
      (node (ref "BAT4") (pin "PWR@1") (pinfunction "+_PWR@1") (pintype "power_in"))
      (node (ref "U$3") (pin "6") (pinfunction "VBAT_6") (pintype "bidirectional"))
    )
    (net (code "109") (name "VDD") (class "Default")
      (node (ref "C20") (pin "2") (pinfunction "C2_2") (pintype "passive"))
      (node (ref "C4") (pin "2") (pinfunction "C2_2") (pintype "passive"))
      (node (ref "C5") (pin "2") (pinfunction "C2_2") (pintype "passive"))
      (node (ref "C6") (pin "2") (pinfunction "C2_2") (pintype "passive"))
      (node (ref "C7") (pin "1") (pinfunction "C1_1") (pintype "passive"))
      (node (ref "JP3") (pin "1") (pinfunction "1_1") (pintype "passive"))
      (node (ref "R35") (pin "2") (pinfunction "2_2") (pintype "passive"))
      (node (ref "R40") (pin "1") (pinfunction "1_1") (pintype "passive"))
      (node (ref "R41") (pin "1") (pinfunction "1_1") (pintype "passive"))
      (node (ref "R42") (pin "1") (pinfunction "1_1") (pintype "passive"))
      (node (ref "R43") (pin "1") (pinfunction "1_1") (pintype "passive"))
      (node (ref "R8") (pin "2") (pinfunction "2_2") (pintype "passive"))
      (node (ref "SJ1") (pin "1") (pinfunction "1_1") (pintype "passive"))
      (node (ref "SJ2") (pin "1") (pinfunction "1_1") (pintype "passive"))
      (node (ref "SJ3") (pin "1") (pinfunction "1_1") (pintype "passive"))
      (node (ref "U$1") (pin "P$8") (pinfunction "IN-_P$8") (pintype "bidirectional"))
      (node (ref "U$12") (pin "1") (pinfunction "VCC_1") (pintype "bidirectional"))
      (node (ref "U$12") (pin "2") (pinfunction "VCC_2") (pintype "bidirectional"))
      (node (ref "U$13") (pin "2") (pinfunction "S_2") (pintype "passive"))
      (node (ref "U$17") (pin "2") (pinfunction "S_2") (pintype "passive"))
      (node (ref "U$18") (pin "2") (pinfunction "S_2") (pintype "passive"))
      (node (ref "U$19") (pin "2") (pinfunction "S_2") (pintype "passive"))
      (node (ref "U$2") (pin "1") (pinfunction "VCC_1") (pintype "bidirectional"))
      (node (ref "U$3") (pin "100") (pinfunction "VDD_4_100") (pintype "bidirectional"))
      (node (ref "U$3") (pin "21") (pinfunction "VREF+_21") (pintype "bidirectional"))
      (node (ref "U$3") (pin "22") (pinfunction "VDDA_22") (pintype "bidirectional"))
      (node (ref "U$3") (pin "28") (pinfunction "VDD_1_28") (pintype "bidirectional"))
      (node (ref "U$3") (pin "50") (pinfunction "VDD_2_50") (pintype "bidirectional"))
      (node (ref "U$3") (pin "75") (pinfunction "VDD_3_75") (pintype "bidirectional"))
    )
    (net (code "110") (name "VIN_MEAS_A2D") (class "Default")
      (node (ref "R6") (pin "1") (pinfunction "1_1") (pintype "passive"))
      (node (ref "R7") (pin "2") (pinfunction "2_2") (pintype "passive"))
      (node (ref "TP3") (pin "TP") (pinfunction "TP_TP") (pintype "input"))
      (node (ref "U$3") (pin "59") (pinfunction "PD12_59") (pintype "bidirectional"))
    )
    (net (code "111") (name "VIN_MEAS_EN") (class "Default")
      (node (ref "R5") (pin "2") (pinfunction "2_2") (pintype "passive"))
      (node (ref "U$3") (pin "41") (pinfunction "PE10_41") (pintype "bidirectional"))
    )
    (net (code "112") (name "VLIPO") (class "Default")
      (node (ref "C15") (pin "1") (pinfunction "C1_1") (pintype "passive"))
      (node (ref "CN2") (pin "1") (pinfunction "2_1") (pintype "passive"))
      (node (ref "D3") (pin "A") (pinfunction "A_A") (pintype "passive"))
      (node (ref "R4") (pin "2") (pinfunction "2_2") (pintype "passive"))
      (node (ref "U$5") (pin "2") (pinfunction "S_2") (pintype "passive"))
      (node (ref "U4") (pin "10") (pinfunction "OUT_10") (pintype "bidirectional"))
    )
    (net (code "113") (name "VPOWER") (class "Default")
      (node (ref "C9") (pin "1") (pinfunction "C1_1") (pintype "passive"))
      (node (ref "D2") (pin "C") (pinfunction "C_C") (pintype "passive"))
      (node (ref "D3") (pin "C") (pinfunction "C_C") (pintype "passive"))
      (node (ref "S4") (pin "1") (pinfunction "1_1") (pintype "bidirectional"))
      (node (ref "U2") (pin "1") (pinfunction "IN_1") (pintype "input"))
    )
    (net (code "114") (name "VUSB") (class "Default")
      (node (ref "C14") (pin "1") (pinfunction "C1_1") (pintype "passive"))
      (node (ref "D2") (pin "A") (pinfunction "A_A") (pintype "passive"))
      (node (ref "R18") (pin "2") (pinfunction "2_2") (pintype "passive"))
      (node (ref "R19") (pin "2") (pinfunction "2_2") (pintype "passive"))
      (node (ref "R28") (pin "2") (pinfunction "2_2") (pintype "passive"))
      (node (ref "U$6") (pin "P$1") (pinfunction "V+_P$1") (pintype "bidirectional"))
      (node (ref "U4") (pin "2") (pinfunction "USB_2") (pintype "bidirectional"))
    )
    (net (code "115") (name "unconnected-(H1-MOUNT-PadB3,0)") (class "Default")
      (node (ref "H1") (pin "B3,0") (pinfunction "MOUNT_B3,0") (pintype "passive"))
    )
    (net (code "116") (name "unconnected-(H2-MOUNT-PadB3,0)") (class "Default")
      (node (ref "H2") (pin "B3,0") (pinfunction "MOUNT_B3,0") (pintype "passive"))
    )
    (net (code "117") (name "unconnected-(H3-MOUNT-PadB3,0)") (class "Default")
      (node (ref "H3") (pin "B3,0") (pinfunction "MOUNT_B3,0") (pintype "passive"))
    )
    (net (code "118") (name "unconnected-(H4-MOUNT-PadB3,0)") (class "Default")
      (node (ref "H4") (pin "B3,0") (pinfunction "MOUNT_B3,0") (pintype "passive"))
    )
    (net (code "119") (name "unconnected-(H5-MOUNT-PadB3,0)") (class "Default")
      (node (ref "H5") (pin "B3,0") (pinfunction "MOUNT_B3,0") (pintype "passive"))
    )
    (net (code "120") (name "unconnected-(H6-MOUNT-PadB3,0)") (class "Default")
      (node (ref "H6") (pin "B3,0") (pinfunction "MOUNT_B3,0") (pintype "passive"))
    )
    (net (code "121") (name "unconnected-(H7-MOUNT-PadB3,0)") (class "Default")
      (node (ref "H7") (pin "B3,0") (pinfunction "MOUNT_B3,0") (pintype "passive"))
    )
    (net (code "122") (name "unconnected-(H8-MOUNT-PadB3,0)") (class "Default")
      (node (ref "H8") (pin "B3,0") (pinfunction "MOUNT_B3,0") (pintype "passive"))
    )
    (net (code "123") (name "unconnected-(S4-Pad3)") (class "Default")
      (node (ref "S4") (pin "3") (pinfunction "3_3") (pintype "bidirectional"))
    )
    (net (code "124") (name "unconnected-(S4-Pad4)") (class "Default")
      (node (ref "S4") (pin "4") (pinfunction "4_4") (pintype "bidirectional"))
    )
    (net (code "125") (name "unconnected-(U$3-PA0-Pad23)") (class "Default")
      (node (ref "U$3") (pin "23") (pinfunction "PA0_23") (pintype "bidirectional"))
    )
    (net (code "126") (name "unconnected-(U$3-PA1-Pad24)") (class "Default")
      (node (ref "U$3") (pin "24") (pinfunction "PA1_24") (pintype "bidirectional"))
    )
    (net (code "127") (name "unconnected-(U$3-PA2-Pad25)") (class "Default")
      (node (ref "U$3") (pin "25") (pinfunction "PA2_25") (pintype "bidirectional"))
    )
    (net (code "128") (name "unconnected-(U$3-PA4-Pad29)") (class "Default")
      (node (ref "U$3") (pin "29") (pinfunction "PA4_29") (pintype "bidirectional"))
    )
    (net (code "129") (name "unconnected-(U$3-PC0-Pad15)") (class "Default")
      (node (ref "U$3") (pin "15") (pinfunction "PC0_15") (pintype "bidirectional"))
    )
    (net (code "130") (name "unconnected-(U$3-PC1-Pad16)") (class "Default")
      (node (ref "U$3") (pin "16") (pinfunction "PC1_16") (pintype "bidirectional"))
    )
    (net (code "131") (name "unconnected-(U$3-PC2-Pad17)") (class "Default")
      (node (ref "U$3") (pin "17") (pinfunction "PC2_17") (pintype "bidirectional"))
    )
    (net (code "132") (name "unconnected-(U$3-PC3-Pad18)") (class "Default")
      (node (ref "U$3") (pin "18") (pinfunction "PC3_18") (pintype "bidirectional"))
    )
    (net (code "133") (name "unconnected-(U$3-PC13-Pad7)") (class "Default")
      (node (ref "U$3") (pin "7") (pinfunction "PC13_7") (pintype "bidirectional"))
    )
    (net (code "134") (name "unconnected-(U$3-PE1-Pad98)") (class "Default")
      (node (ref "U$3") (pin "98") (pinfunction "PE1_98") (pintype "bidirectional"))
    )
    (net (code "135") (name "unconnected-(U$3-PF2-Pad19)") (class "Default")
      (node (ref "U$3") (pin "19") (pinfunction "PF2_19") (pintype "bidirectional"))
    )
    (net (code "136") (name "unconnected-(U$3-PF9-Pad10)") (class "Default")
      (node (ref "U$3") (pin "10") (pinfunction "PF9_10") (pintype "bidirectional"))
    )
    (net (code "137") (name "unconnected-(U$3-PF10-Pad11)") (class "Default")
      (node (ref "U$3") (pin "11") (pinfunction "PF10_11") (pintype "bidirectional"))
    )
    (net (code "138") (name "unconnected-(U$4-NC0-PadP$7)") (class "Default")
      (node (ref "U$4") (pin "P$7") (pinfunction "NC0_P$7") (pintype "bidirectional"))
    )
    (net (code "139") (name "unconnected-(U$4-NC1-PadP$8)") (class "Default")
      (node (ref "U$4") (pin "P$8") (pinfunction "NC1_P$8") (pintype "bidirectional"))
    )
    (net (code "140") (name "unconnected-(U$4-P0.00-PadP$14)") (class "Default")
      (node (ref "U$4") (pin "P$14") (pinfunction "P0.00_P$14") (pintype "bidirectional"))
    )
    (net (code "141") (name "unconnected-(U$4-P0.02-PadP$16)") (class "Default")
      (node (ref "U$4") (pin "P$16") (pinfunction "P0.02_P$16") (pintype "bidirectional"))
    )
    (net (code "142") (name "unconnected-(U$4-P0.03-PadP$17)") (class "Default")
      (node (ref "U$4") (pin "P$17") (pinfunction "P0.03_P$17") (pintype "bidirectional"))
    )
    (net (code "143") (name "unconnected-(U$4-P0.04-PadP$18)") (class "Default")
      (node (ref "U$4") (pin "P$18") (pinfunction "P0.04_P$18") (pintype "bidirectional"))
    )
    (net (code "144") (name "unconnected-(U$4-P0.05-PadP$19)") (class "Default")
      (node (ref "U$4") (pin "P$19") (pinfunction "P0.05_P$19") (pintype "bidirectional"))
    )
    (net (code "145") (name "unconnected-(U$4-P0.06-PadP$20)") (class "Default")
      (node (ref "U$4") (pin "P$20") (pinfunction "P0.06_P$20") (pintype "bidirectional"))
    )
    (net (code "146") (name "unconnected-(U$4-P0.12-PadP$26)") (class "Default")
      (node (ref "U$4") (pin "P$26") (pinfunction "P0.12_P$26") (pintype "bidirectional"))
    )
    (net (code "147") (name "unconnected-(U$4-P0.13-PadP$27)") (class "Default")
      (node (ref "U$4") (pin "P$27") (pinfunction "P0.13_P$27") (pintype "bidirectional"))
    )
    (net (code "148") (name "unconnected-(U$4-P0.14-PadP$28)") (class "Default")
      (node (ref "U$4") (pin "P$28") (pinfunction "P0.14_P$28") (pintype "bidirectional"))
    )
    (net (code "149") (name "unconnected-(U$4-P0.15-PadP$29)") (class "Default")
      (node (ref "U$4") (pin "P$29") (pinfunction "P0.15_P$29") (pintype "bidirectional"))
    )
    (net (code "150") (name "unconnected-(U$4-P0.18-PadP$35)") (class "Default")
      (node (ref "U$4") (pin "P$35") (pinfunction "P0.18_P$35") (pintype "bidirectional"))
    )
    (net (code "151") (name "unconnected-(U$4-P0.20-PadP$36)") (class "Default")
      (node (ref "U$4") (pin "P$36") (pinfunction "P0.20_P$36") (pintype "bidirectional"))
    )
    (net (code "152") (name "unconnected-(U$4-P0.28-PadP$9)") (class "Default")
      (node (ref "U$4") (pin "P$9") (pinfunction "P0.28_P$9") (pintype "bidirectional"))
    )
    (net (code "153") (name "unconnected-(U$4-P0.29-PadP$10)") (class "Default")
      (node (ref "U$4") (pin "P$10") (pinfunction "P0.29_P$10") (pintype "bidirectional"))
    )
    (net (code "154") (name "unconnected-(U$4-P0.30-PadP$13)") (class "Default")
      (node (ref "U$4") (pin "P$13") (pinfunction "P0.30_P$13") (pintype "bidirectional"))
    )
    (net (code "155") (name "unconnected-(U$10-BOOT_SEL-PadP$14)") (class "Default")
      (node (ref "U$10") (pin "P$14") (pinfunction "BOOT_SEL_P$14") (pintype "bidirectional"))
    )
    (net (code "156") (name "unconnected-(U$10-CSN0-PadP$7)") (class "Default")
      (node (ref "U$10") (pin "P$7") (pinfunction "CSN0_P$7") (pintype "bidirectional"))
    )
    (net (code "157") (name "unconnected-(U$10-CSN1-PadP$8)") (class "Default")
      (node (ref "U$10") (pin "P$8") (pinfunction "CSN1_P$8") (pintype "bidirectional"))
    )
    (net (code "158") (name "unconnected-(U$10-CSN2-PadP$16)") (class "Default")
      (node (ref "U$10") (pin "P$16") (pinfunction "CSN2_P$16") (pintype "bidirectional"))
    )
    (net (code "159") (name "unconnected-(U$10-GPIO14-PadP$4)") (class "Default")
      (node (ref "U$10") (pin "P$4") (pinfunction "GPIO14_P$4") (pintype "bidirectional"))
    )
    (net (code "160") (name "unconnected-(U$10-MISO-PadP$5)") (class "Default")
      (node (ref "U$10") (pin "P$5") (pinfunction "MISO_P$5") (pintype "bidirectional"))
    )
    (net (code "161") (name "unconnected-(U$10-MOSI-PadP$6)") (class "Default")
      (node (ref "U$10") (pin "P$6") (pinfunction "MOSI_P$6") (pintype "bidirectional"))
    )
    (net (code "162") (name "unconnected-(U$10-PWM-PadP$10)") (class "Default")
      (node (ref "U$10") (pin "P$10") (pinfunction "PWM_P$10") (pintype "bidirectional"))
    )
    (net (code "163") (name "unconnected-(U$10-SCK-PadP$19)") (class "Default")
      (node (ref "U$10") (pin "P$19") (pinfunction "SCK_P$19") (pintype "bidirectional"))
    )
    (net (code "164") (name "unconnected-(U$10-SCL-PadP$20)") (class "Default")
      (node (ref "U$10") (pin "P$20") (pinfunction "SCL_P$20") (pintype "bidirectional"))
    )
    (net (code "165") (name "unconnected-(U$10-SDA-PadP$9)") (class "Default")
      (node (ref "U$10") (pin "P$9") (pinfunction "SDA_P$9") (pintype "bidirectional"))
    )
    (net (code "166") (name "unconnected-(U$10-VCC5V_OUT-PadP$23)") (class "Default")
      (node (ref "U$10") (pin "P$23") (pinfunction "VCC5V_OUT_P$23") (pintype "bidirectional"))
    )
    (net (code "167") (name "unconnected-(U$10-VCC33_OUT-PadP$22)") (class "Default")
      (node (ref "U$10") (pin "P$22") (pinfunction "VCC33_OUT_P$22") (pintype "bidirectional"))
    )
    (net (code "168") (name "unconnected-(U$12-NC{slash}DBACK-Pad19)") (class "Default")
      (node (ref "U$12") (pin "19") (pinfunction "NC/DBACK_19") (pintype "bidirectional"))
    )
    (net (code "169") (name "unconnected-(U$12-NC{slash}DBGRQ-Pad17)") (class "Default")
      (node (ref "U$12") (pin "17") (pinfunction "NC/DBGRQ_17") (pintype "bidirectional"))
    )
    (net (code "170") (name "unconnected-(U$15-GND-DETECT-Pad9)") (class "Default")
      (node (ref "U$15") (pin "9") (pinfunction "GND-DETECT_9") (pintype "bidirectional"))
    )
    (net (code "171") (name "unconnected-(U$15-NC{slash}TDI-Pad8)") (class "Default")
      (node (ref "U$15") (pin "8") (pinfunction "NC/TDI_8") (pintype "bidirectional"))
    )
    (net (code "172") (name "unconnected-(U$15-SWO{slash}TDO-Pad6)") (class "Default")
      (node (ref "U$15") (pin "6") (pinfunction "SWO/TDO_6") (pintype "bidirectional"))
    )
    (net (code "173") (name "unconnected-(U$15-VCC-Pad1)") (class "Default")
      (node (ref "U$15") (pin "1") (pinfunction "VCC_1") (pintype "bidirectional"))
    )
    (net (code "174") (name "unconnected-(U$15-~{RESET}-Pad10)") (class "Default")
      (node (ref "U$15") (pin "10") (pinfunction "~{RESET}_10") (pintype "bidirectional"))
    )
    (net (code "175") (name "unconnected-(U3-NC-PadRSV1)") (class "Default")
      (node (ref "U3") (pin "RSV1") (pinfunction "NC_RSV1") (pintype "bidirectional"))
    )
    (net (code "176") (name "unconnected-(U3-RSV-PadRSV2)") (class "Default")
      (node (ref "U3") (pin "RSV2") (pinfunction "RSV_RSV2") (pintype "bidirectional"))
    )
    (net (code "177") (name "unconnected-(U4-AC-Pad1)") (class "Default")
      (node (ref "U4") (pin "1") (pinfunction "AC_1") (pintype "bidirectional"))
    )
  )
)
